# dashboard.net
KiCad netlist of a schematic drawn in EAGLE
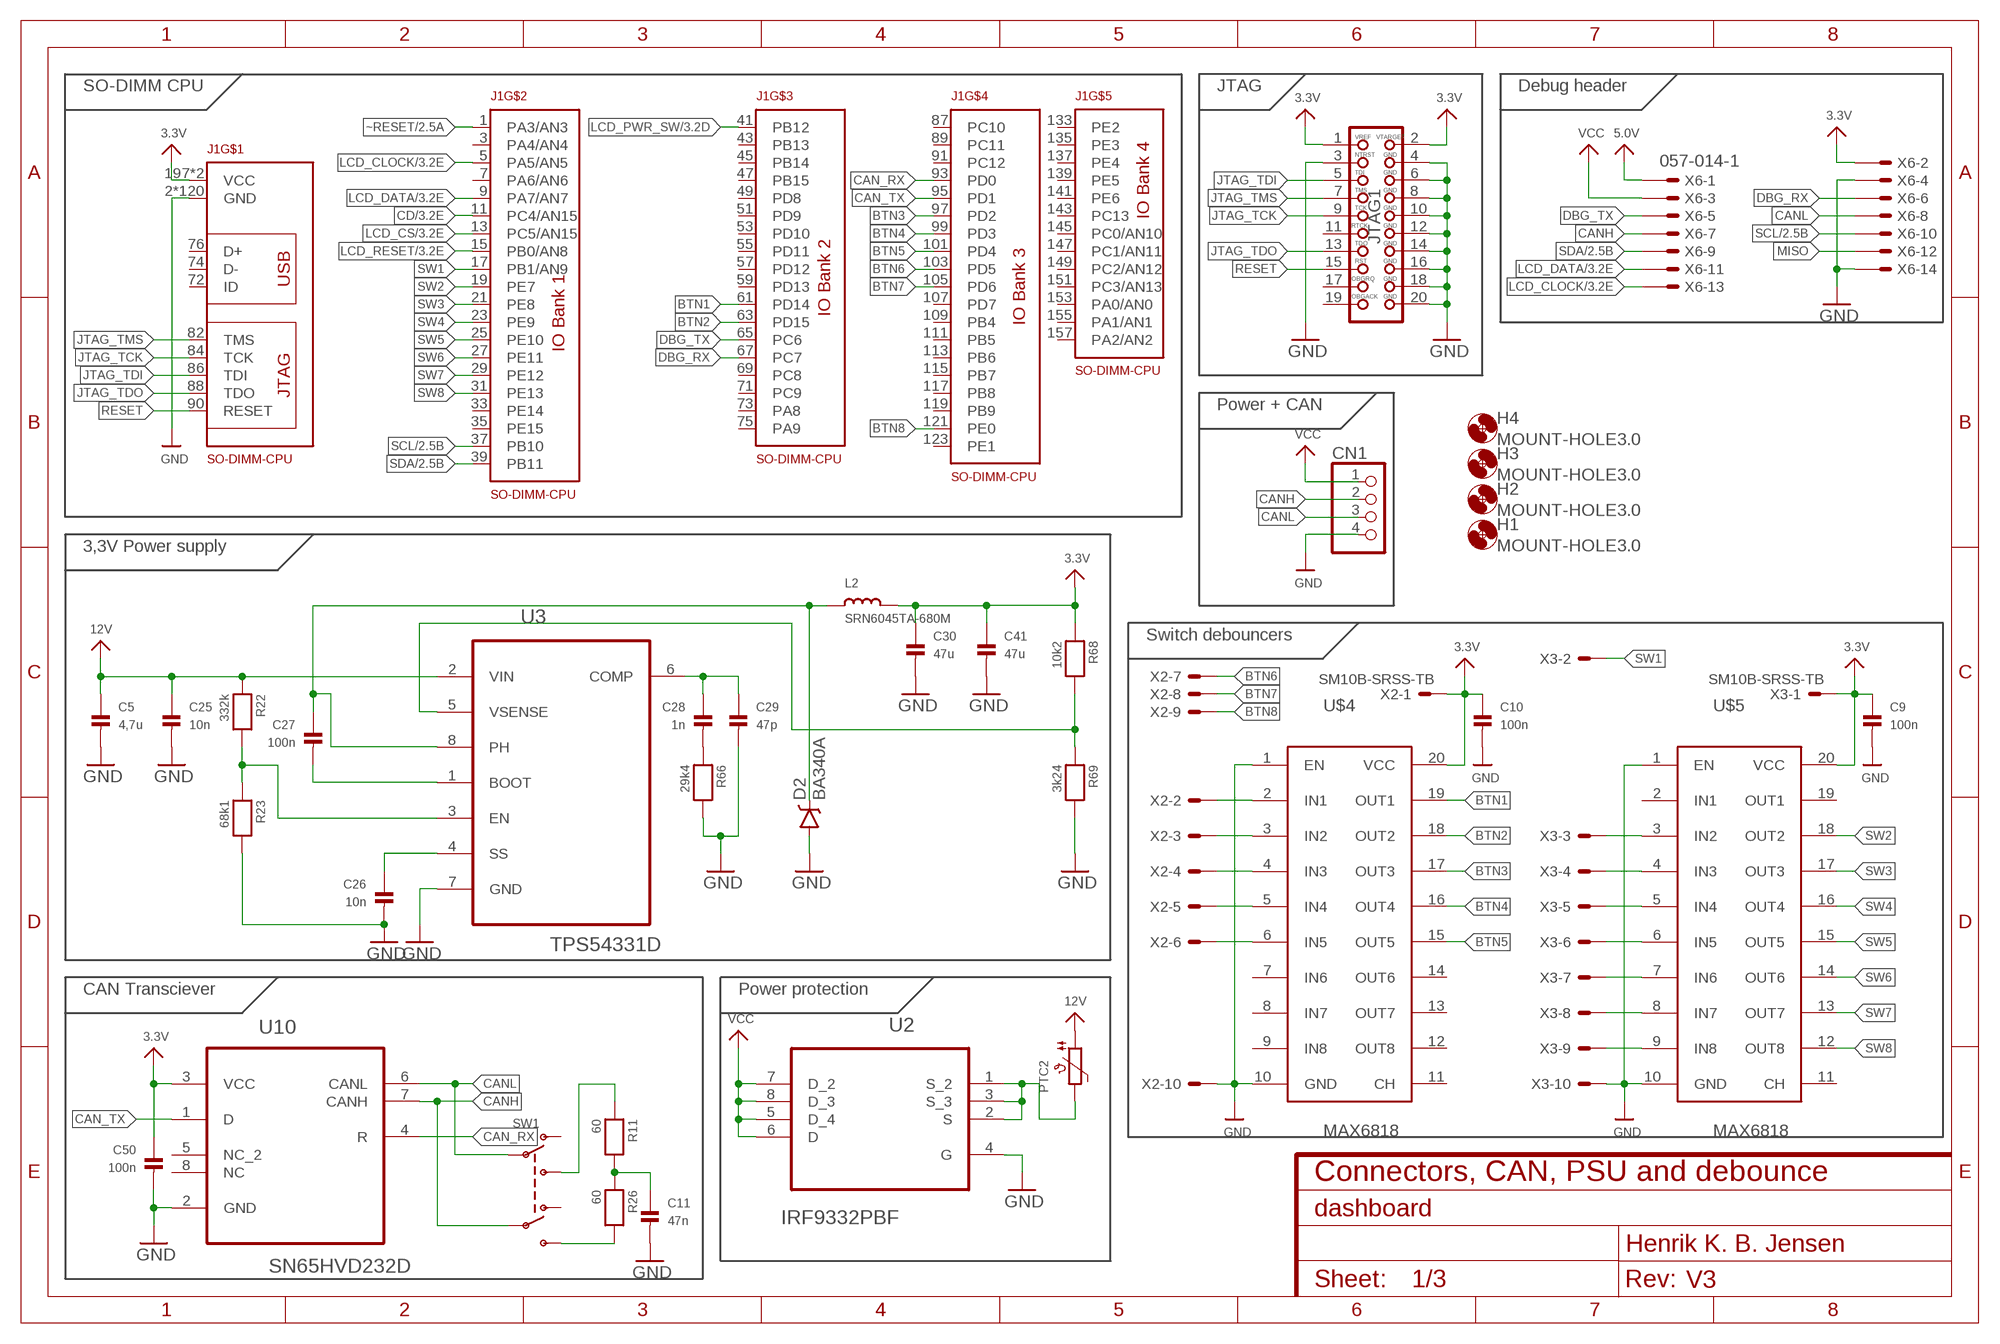
[diagram p0: schematic, sheet 1]
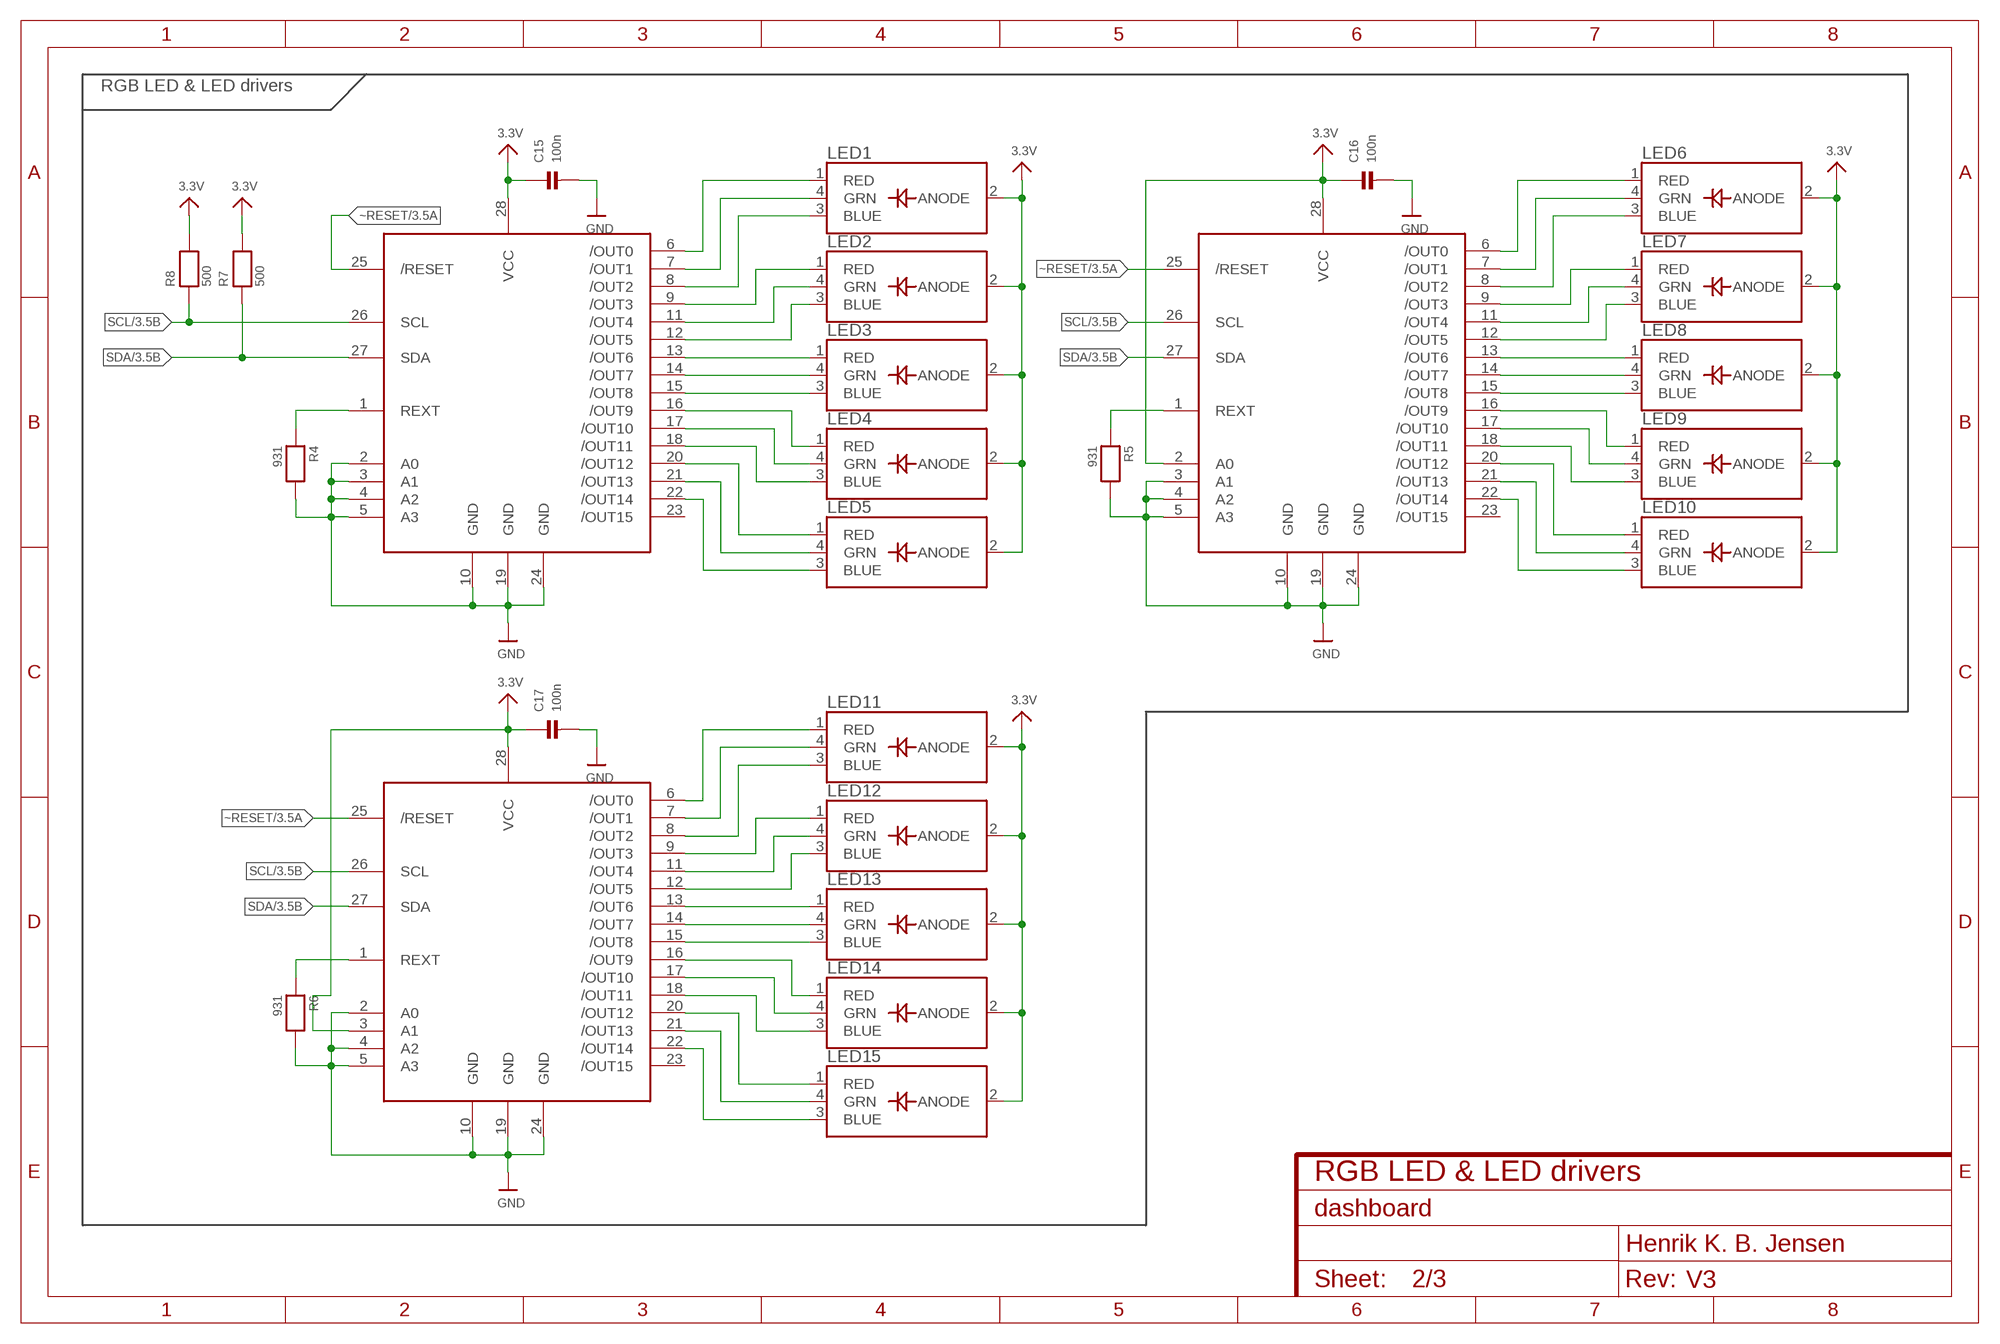
[diagram p1: schematic, sheet 2]
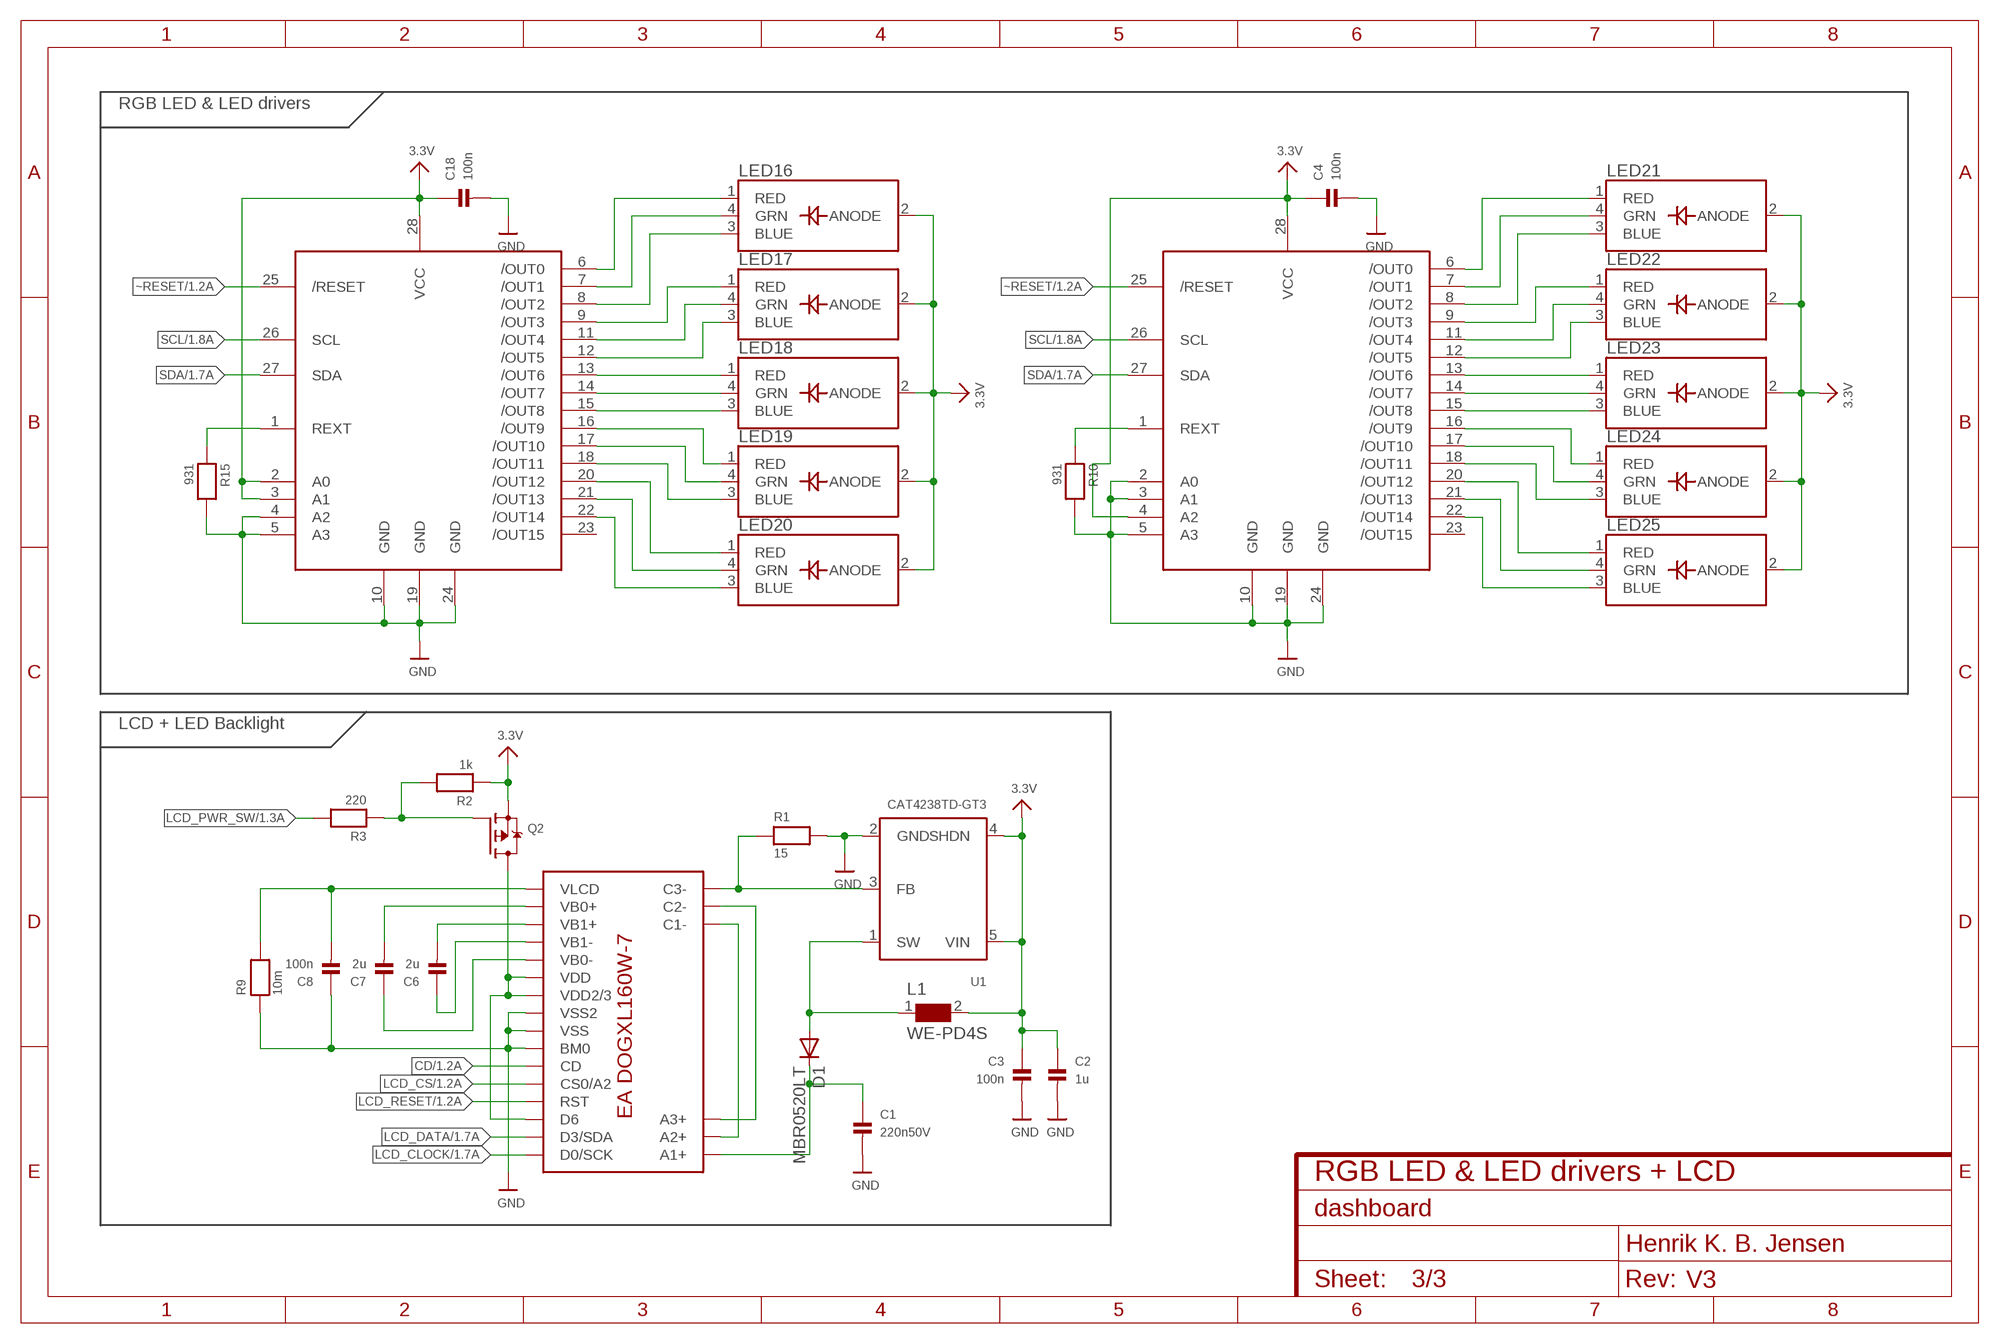
[diagram p2: schematic, sheet 3]

(export (version "E")
  (design (tool "Eeschema 10.0.6"))
  (components
    (comp (ref "C5")
      (value "4,7u")
      (footprint "eagle-import:_0805")
      (libsource (lib "eagle-import") (part "CAP_CERAMIC_0805"))
    )
    (comp (ref "C9")
      (value "100n")
      (footprint "eagle-import:_0603")
      (libsource (lib "eagle-import") (part "CAP_CERAMIC_0603"))
    )
    (comp (ref "C10")
      (value "100n")
      (footprint "eagle-import:_0603")
      (libsource (lib "eagle-import") (part "CAP_CERAMIC_0603"))
    )
    (comp (ref "C11")
      (value "47n")
      (footprint "eagle-import:_0603")
      (libsource (lib "eagle-import") (part "CAP_CERAMIC_0603"))
    )
    (comp (ref "C25")
      (value "10n")
      (footprint "eagle-import:_0603")
      (libsource (lib "eagle-import") (part "CAP_CERAMIC_0603"))
    )
    (comp (ref "C26")
      (value "10n")
      (footprint "eagle-import:_0603")
      (libsource (lib "eagle-import") (part "CAP_CERAMIC_0603"))
    )
    (comp (ref "C27")
      (value "100n")
      (footprint "eagle-import:_0603")
      (libsource (lib "eagle-import") (part "CAP_CERAMIC_0603"))
    )
    (comp (ref "C28")
      (value "1n")
      (footprint "eagle-import:_0603")
      (libsource (lib "eagle-import") (part "CAP_CERAMIC_0603"))
    )
    (comp (ref "C29")
      (value "47p")
      (footprint "eagle-import:_0603")
      (libsource (lib "eagle-import") (part "CAP_CERAMIC_0603"))
    )
    (comp (ref "C30")
      (value "47u")
      (footprint "eagle-import:_0805")
      (libsource (lib "eagle-import") (part "CAP_CERAMIC_0805"))
    )
    (comp (ref "C41")
      (value "47u")
      (footprint "eagle-import:_0805")
      (libsource (lib "eagle-import") (part "CAP_CERAMIC_0805"))
    )
    (comp (ref "C50")
      (value "100n")
      (footprint "eagle-import:_0603")
      (libsource (lib "eagle-import") (part "CAP_CERAMIC_0603"))
    )
    (comp (ref "CN1")
      (value "JST_4PIN")
      (footprint "eagle-import:JSTPH4")
      (libsource (lib "eagle-import") (part "JST_4PIN"))
    )
    (comp (ref "D2")
      (value "BA340A")
      (footprint "eagle-import:SMA-DIODE")
      (libsource (lib "eagle-import") (part "B340A"))
    )
    (comp (ref "H1")
      (value "MOUNT-HOLE3.0")
      (footprint "eagle-import:3,0")
      (libsource (lib "eagle-import") (part "MOUNT-HOLE3.0"))
    )
    (comp (ref "H2")
      (value "MOUNT-HOLE3.0")
      (footprint "eagle-import:3,0")
      (libsource (lib "eagle-import") (part "MOUNT-HOLE3.0"))
    )
    (comp (ref "H3")
      (value "MOUNT-HOLE3.0")
      (footprint "eagle-import:3,0")
      (libsource (lib "eagle-import") (part "MOUNT-HOLE3.0"))
    )
    (comp (ref "H4")
      (value "MOUNT-HOLE3.0")
      (footprint "eagle-import:3,0")
      (libsource (lib "eagle-import") (part "MOUNT-HOLE3.0"))
    )
    (comp (ref "J1")
      (value "SO-DIMM-CPU")
      (footprint "eagle-import:SODIMM-CONNECTOR-2.5V")
      (libsource (lib "eagle-import") (part "SO-DIMM-CPU"))
    )
    (comp (ref "JTAG1")
      (value "JTAG-ARM")
      (footprint "eagle-import:JTAG-ARM")
      (libsource (lib "eagle-import") (part "JTAG-ARM"))
    )
    (comp (ref "L2")
      (value "SRN6045TA-680M")
      (footprint "eagle-import:INDUCTOR_6X6MM_TDK_VLC6045")
      (libsource (lib "eagle-import") (part "INDUCTORTDK_VLC6045"))
    )
    (comp (ref "PTC2")
      (value "PTC1812")
      (footprint "eagle-import:PTC1812")
      (libsource (lib "eagle-import") (part "PTC1812"))
    )
    (comp (ref "R11")
      (value "60")
      (footprint "eagle-import:_0603")
      (libsource (lib "eagle-import") (part "RESISTOR_0603"))
    )
    (comp (ref "R22")
      (value "332k")
      (footprint "eagle-import:_0603")
      (libsource (lib "eagle-import") (part "RESISTOR_0603"))
    )
    (comp (ref "R23")
      (value "68k1")
      (footprint "eagle-import:_0603")
      (libsource (lib "eagle-import") (part "RESISTOR_0603"))
    )
    (comp (ref "R26")
      (value "60")
      (footprint "eagle-import:_0603")
      (libsource (lib "eagle-import") (part "RESISTOR_0603"))
    )
    (comp (ref "R66")
      (value "29k4")
      (footprint "eagle-import:_0603")
      (libsource (lib "eagle-import") (part "RESISTOR_0603"))
    )
    (comp (ref "R68")
      (value "10k2")
      (footprint "eagle-import:_0603")
      (libsource (lib "eagle-import") (part "RESISTOR_0603"))
    )
    (comp (ref "R69")
      (value "3k24")
      (footprint "eagle-import:_0603")
      (libsource (lib "eagle-import") (part "RESISTOR_0603"))
    )
    (comp (ref "SW1")
      (value "SWITCH_DPDT")
      (footprint "eagle-import:DPDT_SMT_JS202011SCQN")
      (libsource (lib "eagle-import") (part "SWITCH_DPDT"))
    )
    (comp (ref "U$4")
      (value "MAX6818")
      (footprint "eagle-import:SOP20")
      (libsource (lib "eagle-import") (part "MAX6818"))
    )
    (comp (ref "U$5")
      (value "MAX6818")
      (footprint "eagle-import:SOP20")
      (libsource (lib "eagle-import") (part "MAX6818"))
    )
    (comp (ref "U2")
      (value "IRF9332PBF")
      (footprint "eagle-import:SOIC127P600X175-8N")
      (libsource (lib "eagle-import") (part "IRF9332PBF"))
    )
    (comp (ref "U3")
      (value "TPS54331D")
      (footprint "eagle-import:SOIC127P600X175-8N")
      (libsource (lib "eagle-import") (part "TPS54331D"))
    )
    (comp (ref "U10")
      (value "SN65HVD232D")
      (footprint "eagle-import:SOIC127P600X175-8N")
      (libsource (lib "eagle-import") (part "SN65HVD232D"))
    )
    (comp (ref "X2")
      (value "SM10B-SRSS-TB")
      (footprint "eagle-import:SM10B-SRSS-TB")
      (libsource (lib "eagle-import") (part "?M10B-SRSS-TBS"))
    )
    (comp (ref "X3")
      (value "SM10B-SRSS-TB")
      (footprint "eagle-import:SM10B-SRSS-TB")
      (libsource (lib "eagle-import") (part "?M10B-SRSS-TBS"))
    )
    (comp (ref "X6")
      (value "057-014-1")
      (footprint "eagle-import:057-014-1")
      (libsource (lib "eagle-import") (part "057-014-1"))
    )
    (comp (ref "C1")
      (value "220n50V")
      (footprint "eagle-import:_0805")
      (libsource (lib "eagle-import") (part "CAP_CERAMIC_0805"))
    )
    (comp (ref "C2")
      (value "1u")
      (footprint "eagle-import:_0805")
      (libsource (lib "eagle-import") (part "CAP_CERAMIC_0805"))
    )
    (comp (ref "C3")
      (value "100n")
      (footprint "eagle-import:_0603")
      (libsource (lib "eagle-import") (part "CAP_CERAMIC_0603"))
    )
    (comp (ref "C4")
      (value "100n")
      (footprint "eagle-import:_0603")
      (libsource (lib "eagle-import") (part "CAP_CERAMIC_0603"))
    )
    (comp (ref "C6")
      (value "2u")
      (footprint "eagle-import:_0805")
      (libsource (lib "eagle-import") (part "CAP_CERAMIC_0805"))
    )
    (comp (ref "C7")
      (value "2u")
      (footprint "eagle-import:_0805")
      (libsource (lib "eagle-import") (part "CAP_CERAMIC_0805"))
    )
    (comp (ref "C8")
      (value "100n")
      (footprint "eagle-import:_0603")
      (libsource (lib "eagle-import") (part "CAP_CERAMIC_0603"))
    )
    (comp (ref "C18")
      (value "100n")
      (footprint "eagle-import:_0603")
      (libsource (lib "eagle-import") (part "CAP_CERAMIC_0603"))
    )
    (comp (ref "D1")
      (value "MBR0520LT")
      (footprint "eagle-import:SOD123")
      (libsource (lib "eagle-import") (part "MBR0520LT"))
    )
    (comp (ref "L1")
      (value "WE-PD4S")
      (footprint "eagle-import:S")
      (fields (field (name "MPN") "7445501"))
      (libsource (lib "eagle-import") (part "WE-PD4_S-7445501"))
    )
    (comp (ref "LED16")
      (value "LED_RGB_PLCC4")
      (footprint "eagle-import:RGBLED_PLCC4")
      (libsource (lib "eagle-import") (part "LED_RGB_PLCC4"))
    )
    (comp (ref "LED17")
      (value "LED_RGB_PLCC4")
      (footprint "eagle-import:RGBLED_PLCC4")
      (libsource (lib "eagle-import") (part "LED_RGB_PLCC4"))
    )
    (comp (ref "LED18")
      (value "LED_RGB_PLCC4")
      (footprint "eagle-import:RGBLED_PLCC4")
      (libsource (lib "eagle-import") (part "LED_RGB_PLCC4"))
    )
    (comp (ref "LED19")
      (value "LED_RGB_PLCC4")
      (footprint "eagle-import:RGBLED_PLCC4")
      (libsource (lib "eagle-import") (part "LED_RGB_PLCC4"))
    )
    (comp (ref "LED20")
      (value "LED_RGB_PLCC4")
      (footprint "eagle-import:RGBLED_PLCC4")
      (libsource (lib "eagle-import") (part "LED_RGB_PLCC4"))
    )
    (comp (ref "LED21")
      (value "LED_RGB_PLCC4")
      (footprint "eagle-import:RGBLED_PLCC4")
      (libsource (lib "eagle-import") (part "LED_RGB_PLCC4"))
    )
    (comp (ref "LED22")
      (value "LED_RGB_PLCC4")
      (footprint "eagle-import:RGBLED_PLCC4")
      (libsource (lib "eagle-import") (part "LED_RGB_PLCC4"))
    )
    (comp (ref "LED23")
      (value "LED_RGB_PLCC4")
      (footprint "eagle-import:RGBLED_PLCC4")
      (libsource (lib "eagle-import") (part "LED_RGB_PLCC4"))
    )
    (comp (ref "LED24")
      (value "LED_RGB_PLCC4")
      (footprint "eagle-import:RGBLED_PLCC4")
      (libsource (lib "eagle-import") (part "LED_RGB_PLCC4"))
    )
    (comp (ref "LED25")
      (value "LED_RGB_PLCC4")
      (footprint "eagle-import:RGBLED_PLCC4")
      (libsource (lib "eagle-import") (part "LED_RGB_PLCC4"))
    )
    (comp (ref "Q2")
      (value "MOSFET-PWIDE")
      (footprint "eagle-import:SOT23-WIDE")
      (libsource (lib "eagle-import") (part "MOSFET-PWIDE"))
    )
    (comp (ref "R1")
      (value "15")
      (footprint "eagle-import:_0603")
      (libsource (lib "eagle-import") (part "RESISTOR_0603"))
    )
    (comp (ref "R2")
      (value "1k")
      (footprint "eagle-import:_0603")
      (libsource (lib "eagle-import") (part "RESISTOR_0603"))
    )
    (comp (ref "R3")
      (value "220")
      (footprint "eagle-import:_0603")
      (libsource (lib "eagle-import") (part "RESISTOR_0603"))
    )
    (comp (ref "R9")
      (value "10m")
      (footprint "eagle-import:_0805")
      (libsource (lib "eagle-import") (part "RESISTOR_0805"))
    )
    (comp (ref "R10")
      (value "931")
      (footprint "eagle-import:_0603")
      (libsource (lib "eagle-import") (part "RESISTOR_0603"))
    )
    (comp (ref "R15")
      (value "931")
      (footprint "eagle-import:_0603")
      (libsource (lib "eagle-import") (part "RESISTOR_0603"))
    )
    (comp (ref "U$8")
      (value "TLC59116")
      (footprint "eagle-import:TSSOP28")
      (libsource (lib "eagle-import") (part "TLC59116"))
    )
    (comp (ref "U$10")
      (value "EA-DOGXL160W-7")
      (footprint "eagle-import:EA-DOGXL160W-7")
      (libsource (lib "eagle-import") (part "EA-DOGXL160W-7"))
    )
    (comp (ref "U$51")
      (value "TLC59116")
      (footprint "eagle-import:TSSOP28")
      (libsource (lib "eagle-import") (part "TLC59116"))
    )
    (comp (ref "U1")
      (value "CAT4238TD-GT3")
      (footprint "eagle-import:SOT23-5")
      (libsource (lib "eagle-import") (part "FAN5331"))
    )
    (comp (ref "C15")
      (value "100n")
      (footprint "eagle-import:_0603")
      (libsource (lib "eagle-import") (part "CAP_CERAMIC_0603"))
    )
    (comp (ref "C16")
      (value "100n")
      (footprint "eagle-import:_0603")
      (libsource (lib "eagle-import") (part "CAP_CERAMIC_0603"))
    )
    (comp (ref "C17")
      (value "100n")
      (footprint "eagle-import:_0603")
      (libsource (lib "eagle-import") (part "CAP_CERAMIC_0603"))
    )
    (comp (ref "LED1")
      (value "LED_RGB_PLCC4")
      (footprint "eagle-import:RGBLED_PLCC4")
      (libsource (lib "eagle-import") (part "LED_RGB_PLCC4"))
    )
    (comp (ref "LED2")
      (value "LED_RGB_PLCC4")
      (footprint "eagle-import:RGBLED_PLCC4")
      (libsource (lib "eagle-import") (part "LED_RGB_PLCC4"))
    )
    (comp (ref "LED3")
      (value "LED_RGB_PLCC4")
      (footprint "eagle-import:RGBLED_PLCC4")
      (libsource (lib "eagle-import") (part "LED_RGB_PLCC4"))
    )
    (comp (ref "LED4")
      (value "LED_RGB_PLCC4")
      (footprint "eagle-import:RGBLED_PLCC4")
      (libsource (lib "eagle-import") (part "LED_RGB_PLCC4"))
    )
    (comp (ref "LED5")
      (value "LED_RGB_PLCC4")
      (footprint "eagle-import:RGBLED_PLCC4")
      (libsource (lib "eagle-import") (part "LED_RGB_PLCC4"))
    )
    (comp (ref "LED6")
      (value "LED_RGB_PLCC4")
      (footprint "eagle-import:RGBLED_PLCC4")
      (libsource (lib "eagle-import") (part "LED_RGB_PLCC4"))
    )
    (comp (ref "LED7")
      (value "LED_RGB_PLCC4")
      (footprint "eagle-import:RGBLED_PLCC4")
      (libsource (lib "eagle-import") (part "LED_RGB_PLCC4"))
    )
    (comp (ref "LED8")
      (value "LED_RGB_PLCC4")
      (footprint "eagle-import:RGBLED_PLCC4")
      (libsource (lib "eagle-import") (part "LED_RGB_PLCC4"))
    )
    (comp (ref "LED9")
      (value "LED_RGB_PLCC4")
      (footprint "eagle-import:RGBLED_PLCC4")
      (libsource (lib "eagle-import") (part "LED_RGB_PLCC4"))
    )
    (comp (ref "LED10")
      (value "LED_RGB_PLCC4")
      (footprint "eagle-import:RGBLED_PLCC4")
      (libsource (lib "eagle-import") (part "LED_RGB_PLCC4"))
    )
    (comp (ref "LED11")
      (value "LED_RGB_PLCC4")
      (footprint "eagle-import:RGBLED_PLCC4")
      (libsource (lib "eagle-import") (part "LED_RGB_PLCC4"))
    )
    (comp (ref "LED12")
      (value "LED_RGB_PLCC4")
      (footprint "eagle-import:RGBLED_PLCC4")
      (libsource (lib "eagle-import") (part "LED_RGB_PLCC4"))
    )
    (comp (ref "LED13")
      (value "LED_RGB_PLCC4")
      (footprint "eagle-import:RGBLED_PLCC4")
      (libsource (lib "eagle-import") (part "LED_RGB_PLCC4"))
    )
    (comp (ref "LED14")
      (value "LED_RGB_PLCC4")
      (footprint "eagle-import:RGBLED_PLCC4")
      (libsource (lib "eagle-import") (part "LED_RGB_PLCC4"))
    )
    (comp (ref "LED15")
      (value "LED_RGB_PLCC4")
      (footprint "eagle-import:RGBLED_PLCC4")
      (libsource (lib "eagle-import") (part "LED_RGB_PLCC4"))
    )
    (comp (ref "R4")
      (value "931")
      (footprint "eagle-import:_0603")
      (libsource (lib "eagle-import") (part "RESISTOR_0603"))
    )
    (comp (ref "R5")
      (value "931")
      (footprint "eagle-import:_0603")
      (libsource (lib "eagle-import") (part "RESISTOR_0603"))
    )
    (comp (ref "R6")
      (value "931")
      (footprint "eagle-import:_0603")
      (libsource (lib "eagle-import") (part "RESISTOR_0603"))
    )
    (comp (ref "R7")
      (value "500")
      (footprint "eagle-import:_0603")
      (libsource (lib "eagle-import") (part "RESISTOR_0603"))
    )
    (comp (ref "R8")
      (value "500")
      (footprint "eagle-import:_0603")
      (libsource (lib "eagle-import") (part "RESISTOR_0603"))
    )
    (comp (ref "U$30")
      (value "TLC59116")
      (footprint "eagle-import:TSSOP28")
      (libsource (lib "eagle-import") (part "TLC59116"))
    )
    (comp (ref "U$33")
      (value "TLC59116")
      (footprint "eagle-import:TSSOP28")
      (libsource (lib "eagle-import") (part "TLC59116"))
    )
    (comp (ref "U$36")
      (value "TLC59116")
      (footprint "eagle-import:TSSOP28")
      (libsource (lib "eagle-import") (part "TLC59116"))
    )
  )
  (nets
    (net (code "1") (name "3.3V") (class "Default")
      (node (ref "C10") (pin "1") (pinfunction "P$1_1") (pintype "passive"))
      (node (ref "C15") (pin "1") (pinfunction "P$1_1") (pintype "passive"))
      (node (ref "C16") (pin "1") (pinfunction "P$1_1") (pintype "passive"))
      (node (ref "C17") (pin "1") (pinfunction "P$1_1") (pintype "passive"))
      (node (ref "C18") (pin "1") (pinfunction "P$1_1") (pintype "passive"))
      (node (ref "C2") (pin "1") (pinfunction "P$1_1") (pintype "passive"))
      (node (ref "C3") (pin "1") (pinfunction "P$1_1") (pintype "passive"))
      (node (ref "C30") (pin "1") (pinfunction "P$1_1") (pintype "passive"))
      (node (ref "C4") (pin "1") (pinfunction "P$1_1") (pintype "passive"))
      (node (ref "C41") (pin "1") (pinfunction "P$1_1") (pintype "passive"))
      (node (ref "C50") (pin "1") (pinfunction "P$1_1") (pintype "passive"))
      (node (ref "C9") (pin "1") (pinfunction "P$1_1") (pintype "passive"))
      (node (ref "J1") (pin "197") (pinfunction "VCC_197") (pintype "bidirectional"))
      (node (ref "J1") (pin "199") (pinfunction "VCC_199") (pintype "bidirectional"))
      (node (ref "JTAG1") (pin "1") (pinfunction "1_1") (pintype "passive"))
      (node (ref "JTAG1") (pin "2") (pinfunction "2_2") (pintype "passive"))
      (node (ref "L1") (pin "2") (pinfunction "2_2") (pintype "passive"))
      (node (ref "L2") (pin "P$2") (pinfunction "2_P$2") (pintype "passive"))
      (node (ref "LED1") (pin "2") (pinfunction "ANODE_2") (pintype "power_in"))
      (node (ref "LED10") (pin "2") (pinfunction "ANODE_2") (pintype "power_in"))
      (node (ref "LED11") (pin "2") (pinfunction "ANODE_2") (pintype "power_in"))
      (node (ref "LED12") (pin "2") (pinfunction "ANODE_2") (pintype "power_in"))
      (node (ref "LED13") (pin "2") (pinfunction "ANODE_2") (pintype "power_in"))
      (node (ref "LED14") (pin "2") (pinfunction "ANODE_2") (pintype "power_in"))
      (node (ref "LED15") (pin "2") (pinfunction "ANODE_2") (pintype "power_in"))
      (node (ref "LED16") (pin "2") (pinfunction "ANODE_2") (pintype "power_in"))
      (node (ref "LED17") (pin "2") (pinfunction "ANODE_2") (pintype "power_in"))
      (node (ref "LED18") (pin "2") (pinfunction "ANODE_2") (pintype "power_in"))
      (node (ref "LED19") (pin "2") (pinfunction "ANODE_2") (pintype "power_in"))
      (node (ref "LED2") (pin "2") (pinfunction "ANODE_2") (pintype "power_in"))
      (node (ref "LED20") (pin "2") (pinfunction "ANODE_2") (pintype "power_in"))
      (node (ref "LED21") (pin "2") (pinfunction "ANODE_2") (pintype "power_in"))
      (node (ref "LED22") (pin "2") (pinfunction "ANODE_2") (pintype "power_in"))
      (node (ref "LED23") (pin "2") (pinfunction "ANODE_2") (pintype "power_in"))
      (node (ref "LED24") (pin "2") (pinfunction "ANODE_2") (pintype "power_in"))
      (node (ref "LED25") (pin "2") (pinfunction "ANODE_2") (pintype "power_in"))
      (node (ref "LED3") (pin "2") (pinfunction "ANODE_2") (pintype "power_in"))
      (node (ref "LED4") (pin "2") (pinfunction "ANODE_2") (pintype "power_in"))
      (node (ref "LED5") (pin "2") (pinfunction "ANODE_2") (pintype "power_in"))
      (node (ref "LED6") (pin "2") (pinfunction "ANODE_2") (pintype "power_in"))
      (node (ref "LED7") (pin "2") (pinfunction "ANODE_2") (pintype "power_in"))
      (node (ref "LED8") (pin "2") (pinfunction "ANODE_2") (pintype "power_in"))
      (node (ref "LED9") (pin "2") (pinfunction "ANODE_2") (pintype "power_in"))
      (node (ref "Q2") (pin "2") (pinfunction "S_2") (pintype "passive"))
      (node (ref "R2") (pin "1") (pinfunction "1_1") (pintype "passive"))
      (node (ref "R68") (pin "1") (pinfunction "1_1") (pintype "passive"))
      (node (ref "R7") (pin "2") (pinfunction "2_2") (pintype "passive"))
      (node (ref "R8") (pin "2") (pinfunction "2_2") (pintype "passive"))
      (node (ref "U$30") (pin "28") (pinfunction "VCC_28") (pintype "bidirectional"))
      (node (ref "U$33") (pin "2") (pinfunction "A0_2") (pintype "bidirectional"))
      (node (ref "U$33") (pin "28") (pinfunction "VCC_28") (pintype "bidirectional"))
      (node (ref "U$36") (pin "28") (pinfunction "VCC_28") (pintype "bidirectional"))
      (node (ref "U$36") (pin "3") (pinfunction "A1_3") (pintype "bidirectional"))
      (node (ref "U$4") (pin "20") (pinfunction "VCC_20") (pintype "power_in"))
      (node (ref "U$5") (pin "20") (pinfunction "VCC_20") (pintype "power_in"))
      (node (ref "U$51") (pin "2") (pinfunction "A0_2") (pintype "bidirectional"))
      (node (ref "U$51") (pin "28") (pinfunction "VCC_28") (pintype "bidirectional"))
      (node (ref "U$51") (pin "3") (pinfunction "A1_3") (pintype "bidirectional"))
      (node (ref "U$8") (pin "28") (pinfunction "VCC_28") (pintype "bidirectional"))
      (node (ref "U$8") (pin "4") (pinfunction "A2_4") (pintype "bidirectional"))
      (node (ref "U1") (pin "4") (pinfunction "SHDN_4") (pintype "bidirectional"))
      (node (ref "U1") (pin "5") (pinfunction "VIN_5") (pintype "bidirectional"))
      (node (ref "U10") (pin "3") (pinfunction "VCC_3") (pintype "power_in"))
      (node (ref "X2") (pin "1") (pinfunction "S_1") (pintype "passive"))
      (node (ref "X3") (pin "1") (pinfunction "S_1") (pintype "passive"))
      (node (ref "X6") (pin "2") (pinfunction "S_2") (pintype "passive"))
    )
    (net (code "2") (name "5.0V") (class "Default")
      (node (ref "X6") (pin "1") (pinfunction "S_1") (pintype "passive"))
    )
    (net (code "3") (name "12V") (class "Default")
      (node (ref "C25") (pin "1") (pinfunction "P$1_1") (pintype "passive"))
      (node (ref "C5") (pin "1") (pinfunction "P$1_1") (pintype "passive"))
      (node (ref "PTC2") (pin "P$1") (pinfunction "1_P$1") (pintype "passive"))
      (node (ref "R22") (pin "1") (pinfunction "1_1") (pintype "passive"))
      (node (ref "U3") (pin "2") (pinfunction "VIN_2") (pintype "input"))
    )
    (net (code "4") (name "BTN1") (class "Default")
      (node (ref "J1") (pin "61") (pinfunction "PD14_61") (pintype "bidirectional"))
      (node (ref "U$4") (pin "19") (pinfunction "OUT1_19") (pintype "bidirectional"))
    )
    (net (code "5") (name "BTN2") (class "Default")
      (node (ref "J1") (pin "63") (pinfunction "PD15_63") (pintype "bidirectional"))
      (node (ref "U$4") (pin "18") (pinfunction "OUT2_18") (pintype "bidirectional"))
    )
    (net (code "6") (name "BTN3") (class "Default")
      (node (ref "J1") (pin "97") (pinfunction "PD2_97") (pintype "bidirectional"))
      (node (ref "U$4") (pin "17") (pinfunction "OUT3_17") (pintype "bidirectional"))
    )
    (net (code "7") (name "BTN4") (class "Default")
      (node (ref "J1") (pin "99") (pinfunction "PD3_99") (pintype "bidirectional"))
      (node (ref "U$4") (pin "16") (pinfunction "OUT4_16") (pintype "bidirectional"))
    )
    (net (code "8") (name "BTN5") (class "Default")
      (node (ref "J1") (pin "101") (pinfunction "PD4_101") (pintype "bidirectional"))
      (node (ref "U$4") (pin "15") (pinfunction "OUT5_15") (pintype "bidirectional"))
    )
    (net (code "9") (name "BTN6") (class "Default")
      (node (ref "J1") (pin "103") (pinfunction "PD5_103") (pintype "bidirectional"))
      (node (ref "X2") (pin "7") (pinfunction "S_7") (pintype "passive"))
    )
    (net (code "10") (name "BTN7") (class "Default")
      (node (ref "J1") (pin "105") (pinfunction "PD6_105") (pintype "bidirectional"))
      (node (ref "X2") (pin "8") (pinfunction "S_8") (pintype "passive"))
    )
    (net (code "11") (name "BTN8") (class "Default")
      (node (ref "J1") (pin "121") (pinfunction "PE0_121") (pintype "bidirectional"))
      (node (ref "X2") (pin "9") (pinfunction "S_9") (pintype "passive"))
    )
    (net (code "12") (name "CANH") (class "Default")
      (node (ref "CN1") (pin "2") (pinfunction "2_2") (pintype "passive"))
      (node (ref "SW1") (pin "P$5") (pinfunction "P2_P$5") (pintype "passive"))
      (node (ref "U10") (pin "7") (pinfunction "CANH_7") (pintype "output"))
      (node (ref "X6") (pin "7") (pinfunction "S_7") (pintype "passive"))
    )
    (net (code "13") (name "CANL") (class "Default")
      (node (ref "CN1") (pin "3") (pinfunction "3_3") (pintype "passive"))
      (node (ref "SW1") (pin "P$2") (pinfunction "P1_P$2") (pintype "passive"))
      (node (ref "U10") (pin "6") (pinfunction "CANL_6") (pintype "output"))
      (node (ref "X6") (pin "8") (pinfunction "S_8") (pintype "passive"))
    )
    (net (code "14") (name "CAN_RX") (class "Default")
      (node (ref "J1") (pin "93") (pinfunction "PD0_93") (pintype "bidirectional"))
      (node (ref "U10") (pin "4") (pinfunction "R_4") (pintype "output"))
    )
    (net (code "15") (name "CAN_TX") (class "Default")
      (node (ref "J1") (pin "95") (pinfunction "PD1_95") (pintype "bidirectional"))
      (node (ref "U10") (pin "1") (pinfunction "D_1") (pintype "input"))
    )
    (net (code "16") (name "CD") (class "Default")
      (node (ref "J1") (pin "11") (pinfunction "PC4/AN15_11") (pintype "bidirectional"))
      (node (ref "U$10") (pin "P$27") (pinfunction "CD_P$27") (pintype "bidirectional"))
    )
    (net (code "17") (name "DBG_RX") (class "Default")
      (node (ref "J1") (pin "67") (pinfunction "PC7_67") (pintype "bidirectional"))
      (node (ref "X6") (pin "6") (pinfunction "S_6") (pintype "passive"))
    )
    (net (code "18") (name "DBG_TX") (class "Default")
      (node (ref "J1") (pin "65") (pinfunction "PC6_65") (pintype "bidirectional"))
      (node (ref "X6") (pin "5") (pinfunction "S_5") (pintype "passive"))
    )
    (net (code "19") (name "GND") (class "Default")
      (node (ref "C1") (pin "2") (pinfunction "P$2_2") (pintype "passive"))
      (node (ref "C10") (pin "2") (pinfunction "P$2_2") (pintype "passive"))
      (node (ref "C11") (pin "2") (pinfunction "P$2_2") (pintype "passive"))
      (node (ref "C15") (pin "2") (pinfunction "P$2_2") (pintype "passive"))
      (node (ref "C16") (pin "2") (pinfunction "P$2_2") (pintype "passive"))
      (node (ref "C17") (pin "2") (pinfunction "P$2_2") (pintype "passive"))
      (node (ref "C18") (pin "2") (pinfunction "P$2_2") (pintype "passive"))
      (node (ref "C2") (pin "2") (pinfunction "P$2_2") (pintype "passive"))
      (node (ref "C25") (pin "2") (pinfunction "P$2_2") (pintype "passive"))
      (node (ref "C26") (pin "2") (pinfunction "P$2_2") (pintype "passive"))
      (node (ref "C29") (pin "2") (pinfunction "P$2_2") (pintype "passive"))
      (node (ref "C3") (pin "2") (pinfunction "P$2_2") (pintype "passive"))
      (node (ref "C30") (pin "2") (pinfunction "P$2_2") (pintype "passive"))
      (node (ref "C4") (pin "2") (pinfunction "P$2_2") (pintype "passive"))
      (node (ref "C41") (pin "2") (pinfunction "P$2_2") (pintype "passive"))
      (node (ref "C5") (pin "2") (pinfunction "P$2_2") (pintype "passive"))
      (node (ref "C50") (pin "2") (pinfunction "P$2_2") (pintype "passive"))
      (node (ref "C8") (pin "1") (pinfunction "P$1_1") (pintype "passive"))
      (node (ref "C9") (pin "2") (pinfunction "P$2_2") (pintype "passive"))
      (node (ref "CN1") (pin "4") (pinfunction "4_4") (pintype "passive"))
      (node (ref "D2") (pin "A") (pinfunction "A_A") (pintype "passive"))
      (node (ref "J1") (pin "10") (pinfunction "GND_10") (pintype "bidirectional"))
      (node (ref "J1") (pin "100") (pinfunction "GND_100") (pintype "bidirectional"))
      (node (ref "J1") (pin "102") (pinfunction "GND_102") (pintype "bidirectional"))
      (node (ref "J1") (pin "104") (pinfunction "GND_104") (pintype "bidirectional"))
      (node (ref "J1") (pin "106") (pinfunction "GND_106") (pintype "bidirectional"))
      (node (ref "J1") (pin "108") (pinfunction "GND_108") (pintype "bidirectional"))
      (node (ref "J1") (pin "110") (pinfunction "GND_110") (pintype "bidirectional"))
      (node (ref "J1") (pin "112") (pinfunction "GND_112") (pintype "bidirectional"))
      (node (ref "J1") (pin "114") (pinfunction "GND_114") (pintype "bidirectional"))
      (node (ref "J1") (pin "116") (pinfunction "GND_116") (pintype "bidirectional"))
      (node (ref "J1") (pin "118") (pinfunction "GND_118") (pintype "bidirectional"))
      (node (ref "J1") (pin "12") (pinfunction "GND_12") (pintype "bidirectional"))
      (node (ref "J1") (pin "120") (pinfunction "GND_120") (pintype "bidirectional"))
      (node (ref "J1") (pin "122") (pinfunction "GND_122") (pintype "bidirectional"))
      (node (ref "J1") (pin "124") (pinfunction "GND_124") (pintype "bidirectional"))
      (node (ref "J1") (pin "125") (pinfunction "GND_125") (pintype "bidirectional"))
      (node (ref "J1") (pin "126") (pinfunction "GND_126") (pintype "bidirectional"))
      (node (ref "J1") (pin "127") (pinfunction "GND_127") (pintype "bidirectional"))
      (node (ref "J1") (pin "128") (pinfunction "GND_128") (pintype "bidirectional"))
      (node (ref "J1") (pin "129") (pinfunction "GND_129") (pintype "bidirectional"))
      (node (ref "J1") (pin "130") (pinfunction "GND_130") (pintype "bidirectional"))
      (node (ref "J1") (pin "131") (pinfunction "GND_131") (pintype "bidirectional"))
      (node (ref "J1") (pin "132") (pinfunction "GND_132") (pintype "bidirectional"))
      (node (ref "J1") (pin "134") (pinfunction "GND_134") (pintype "bidirectional"))
      (node (ref "J1") (pin "136") (pinfunction "GND_136") (pintype "bidirectional"))
      (node (ref "J1") (pin "138") (pinfunction "GND_138") (pintype "bidirectional"))
      (node (ref "J1") (pin "14") (pinfunction "GND_14") (pintype "bidirectional"))
      (node (ref "J1") (pin "140") (pinfunction "GND_140") (pintype "bidirectional"))
      (node (ref "J1") (pin "142") (pinfunction "GND_142") (pintype "bidirectional"))
      (node (ref "J1") (pin "144") (pinfunction "GND_144") (pintype "bidirectional"))
      (node (ref "J1") (pin "146") (pinfunction "GND_146") (pintype "bidirectional"))
      (node (ref "J1") (pin "148") (pinfunction "GND_148") (pintype "bidirectional"))
      (node (ref "J1") (pin "150") (pinfunction "GND_150") (pintype "bidirectional"))
      (node (ref "J1") (pin "152") (pinfunction "GND_152") (pintype "bidirectional"))
      (node (ref "J1") (pin "154") (pinfunction "GND_154") (pintype "bidirectional"))
      (node (ref "J1") (pin "156") (pinfunction "GND_156") (pintype "bidirectional"))
      (node (ref "J1") (pin "158") (pinfunction "GND_158") (pintype "bidirectional"))
      (node (ref "J1") (pin "159") (pinfunction "GND_159") (pintype "bidirectional"))
      (node (ref "J1") (pin "16") (pinfunction "GND_16") (pintype "bidirectional"))
      (node (ref "J1") (pin "160") (pinfunction "GND_160") (pintype "bidirectional"))
      (node (ref "J1") (pin "161") (pinfunction "GND_161") (pintype "bidirectional"))
      (node (ref "J1") (pin "162") (pinfunction "GND_162") (pintype "bidirectional"))
      (node (ref "J1") (pin "163") (pinfunction "GND_163") (pintype "bidirectional"))
      (node (ref "J1") (pin "164") (pinfunction "GND_164") (pintype "bidirectional"))
      (node (ref "J1") (pin "165") (pinfunction "GND_165") (pintype "bidirectional"))
      (node (ref "J1") (pin "166") (pinfunction "GND_166") (pintype "bidirectional"))
      (node (ref "J1") (pin "167") (pinfunction "GND_167") (pintype "bidirectional"))
      (node (ref "J1") (pin "168") (pinfunction "GND_168") (pintype "bidirectional"))
      (node (ref "J1") (pin "169") (pinfunction "GND_169") (pintype "bidirectional"))
      (node (ref "J1") (pin "170") (pinfunction "GND_170") (pintype "bidirectional"))
      (node (ref "J1") (pin "171") (pinfunction "GND_171") (pintype "bidirectional"))
      (node (ref "J1") (pin "172") (pinfunction "GND_172") (pintype "bidirectional"))
      (node (ref "J1") (pin "173") (pinfunction "GND_173") (pintype "bidirectional"))
      (node (ref "J1") (pin "174") (pinfunction "GND_174") (pintype "bidirectional"))
      (node (ref "J1") (pin "175") (pinfunction "GND_175") (pintype "bidirectional"))
      (node (ref "J1") (pin "176") (pinfunction "GND_176") (pintype "bidirectional"))
      (node (ref "J1") (pin "177") (pinfunction "GND_177") (pintype "bidirectional"))
      (node (ref "J1") (pin "178") (pinfunction "GND_178") (pintype "bidirectional"))
      (node (ref "J1") (pin "179") (pinfunction "GND_179") (pintype "bidirectional"))
      (node (ref "J1") (pin "18") (pinfunction "GND_18") (pintype "bidirectional"))
      (node (ref "J1") (pin "180") (pinfunction "GND_180") (pintype "bidirectional"))
      (node (ref "J1") (pin "181") (pinfunction "GND_181") (pintype "bidirectional"))
      (node (ref "J1") (pin "182") (pinfunction "GND_182") (pintype "bidirectional"))
      (node (ref "J1") (pin "183") (pinfunction "GND_183") (pintype "bidirectional"))
      (node (ref "J1") (pin "184") (pinfunction "GND_184") (pintype "bidirectional"))
      (node (ref "J1") (pin "185") (pinfunction "GND_185") (pintype "bidirectional"))
      (node (ref "J1") (pin "186") (pinfunction "GND_186") (pintype "bidirectional"))
      (node (ref "J1") (pin "187") (pinfunction "GND_187") (pintype "bidirectional"))
      (node (ref "J1") (pin "188") (pinfunction "GND_188") (pintype "bidirectional"))
      (node (ref "J1") (pin "189") (pinfunction "GND_189") (pintype "bidirectional"))
      (node (ref "J1") (pin "190") (pinfunction "GND_190") (pintype "bidirectional"))
      (node (ref "J1") (pin "191") (pinfunction "GND_191") (pintype "bidirectional"))
      (node (ref "J1") (pin "192") (pinfunction "GND_192") (pintype "bidirectional"))
      (node (ref "J1") (pin "193") (pinfunction "GND_193") (pintype "bidirectional"))
      (node (ref "J1") (pin "194") (pinfunction "GND_194") (pintype "bidirectional"))
      (node (ref "J1") (pin "195") (pinfunction "GND_195") (pintype "bidirectional"))
      (node (ref "J1") (pin "196") (pinfunction "GND_196") (pintype "bidirectional"))
      (node (ref "J1") (pin "198") (pinfunction "GND_198") (pintype "bidirectional"))
      (node (ref "J1") (pin "2") (pinfunction "GND_2") (pintype "bidirectional"))
      (node (ref "J1") (pin "20") (pinfunction "GND_20") (pintype "bidirectional"))
      (node (ref "J1") (pin "200") (pinfunction "GND_200") (pintype "bidirectional"))
      (node (ref "J1") (pin "22") (pinfunction "GND_22") (pintype "bidirectional"))
      (node (ref "J1") (pin "24") (pinfunction "GND_24") (pintype "bidirectional"))
      (node (ref "J1") (pin "26") (pinfunction "GND_26") (pintype "bidirectional"))
      (node (ref "J1") (pin "28") (pinfunction "GND_28") (pintype "bidirectional"))
      (node (ref "J1") (pin "30") (pinfunction "GND_30") (pintype "bidirectional"))
      (node (ref "J1") (pin "32") (pinfunction "GND_32") (pintype "bidirectional"))
      (node (ref "J1") (pin "34") (pinfunction "GND_34") (pintype "bidirectional"))
      (node (ref "J1") (pin "36") (pinfunction "GND_36") (pintype "bidirectional"))
      (node (ref "J1") (pin "38") (pinfunction "GND_38") (pintype "bidirectional"))
      (node (ref "J1") (pin "4") (pinfunction "GND_4") (pintype "bidirectional"))
      (node (ref "J1") (pin "40") (pinfunction "GND_40") (pintype "bidirectional"))
      (node (ref "J1") (pin "42") (pinfunction "GND_42") (pintype "bidirectional"))
      (node (ref "J1") (pin "44") (pinfunction "GND_44") (pintype "bidirectional"))
      (node (ref "J1") (pin "46") (pinfunction "GND_46") (pintype "bidirectional"))
      (node (ref "J1") (pin "48") (pinfunction "GND_48") (pintype "bidirectional"))
      (node (ref "J1") (pin "50") (pinfunction "GND_50") (pintype "bidirectional"))
      (node (ref "J1") (pin "52") (pinfunction "GND_52") (pintype "bidirectional"))
      (node (ref "J1") (pin "54") (pinfunction "GND_54") (pintype "bidirectional"))
      (node (ref "J1") (pin "56") (pinfunction "GND_56") (pintype "bidirectional"))
      (node (ref "J1") (pin "58") (pinfunction "GND_58") (pintype "bidirectional"))
      (node (ref "J1") (pin "6") (pinfunction "GND_6") (pintype "bidirectional"))
      (node (ref "J1") (pin "60") (pinfunction "GND_60") (pintype "bidirectional"))
      (node (ref "J1") (pin "62") (pinfunction "GND_62") (pintype "bidirectional"))
      (node (ref "J1") (pin "64") (pinfunction "GND_64") (pintype "bidirectional"))
      (node (ref "J1") (pin "66") (pinfunction "GND_66") (pintype "bidirectional"))
      (node (ref "J1") (pin "68") (pinfunction "GND_68") (pintype "bidirectional"))
      (node (ref "J1") (pin "70") (pinfunction "GND_70") (pintype "bidirectional"))
      (node (ref "J1") (pin "77") (pinfunction "GND_77") (pintype "bidirectional"))
      (node (ref "J1") (pin "78") (pinfunction "GND_78") (pintype "bidirectional"))
      (node (ref "J1") (pin "79") (pinfunction "GND_79") (pintype "bidirectional"))
      (node (ref "J1") (pin "8") (pinfunction "GND_8") (pintype "bidirectional"))
      (node (ref "J1") (pin "80") (pinfunction "GND_80") (pintype "bidirectional"))
      (node (ref "J1") (pin "81") (pinfunction "GND_81") (pintype "bidirectional"))
      (node (ref "J1") (pin "83") (pinfunction "GND_83") (pintype "bidirectional"))
      (node (ref "J1") (pin "85") (pinfunction "GND_85") (pintype "bidirectional"))
      (node (ref "J1") (pin "92") (pinfunction "GND_92") (pintype "bidirectional"))
      (node (ref "J1") (pin "94") (pinfunction "GND_94") (pintype "bidirectional"))
      (node (ref "J1") (pin "96") (pinfunction "GND_96") (pintype "bidirectional"))
      (node (ref "J1") (pin "98") (pinfunction "GND_98") (pintype "bidirectional"))
      (node (ref "JTAG1") (pin "10") (pinfunction "10_10") (pintype "passive"))
      (node (ref "JTAG1") (pin "12") (pinfunction "12_12") (pintype "passive"))
      (node (ref "JTAG1") (pin "14") (pinfunction "14_14") (pintype "passive"))
      (node (ref "JTAG1") (pin "16") (pinfunction "16_16") (pintype "passive"))
      (node (ref "JTAG1") (pin "18") (pinfunction "18_18") (pintype "passive"))
      (node (ref "JTAG1") (pin "20") (pinfunction "20_20") (pintype "passive"))
      (node (ref "JTAG1") (pin "3") (pinfunction "3_3") (pintype "passive"))
      (node (ref "JTAG1") (pin "4") (pinfunction "4_4") (pintype "passive"))
      (node (ref "JTAG1") (pin "6") (pinfunction "6_6") (pintype "passive"))
      (node (ref "JTAG1") (pin "8") (pinfunction "8_8") (pintype "passive"))
      (node (ref "R1") (pin "2") (pinfunction "2_2") (pintype "passive"))
      (node (ref "R10") (pin "2") (pinfunction "2_2") (pintype "passive"))
      (node (ref "R15") (pin "2") (pinfunction "2_2") (pintype "passive"))
      (node (ref "R23") (pin "2") (pinfunction "2_2") (pintype "passive"))
      (node (ref "R4") (pin "2") (pinfunction "2_2") (pintype "passive"))
      (node (ref "R5") (pin "2") (pinfunction "2_2") (pintype "passive"))
      (node (ref "R6") (pin "2") (pinfunction "2_2") (pintype "passive"))
      (node (ref "R66") (pin "2") (pinfunction "2_2") (pintype "passive"))
      (node (ref "R69") (pin "2") (pinfunction "2_2") (pintype "passive"))
      (node (ref "R9") (pin "1") (pinfunction "1_1") (pintype "passive"))
      (node (ref "U$10") (pin "P$24") (pinfunction "VSS2_P$24") (pintype "bidirectional"))
      (node (ref "U$10") (pin "P$25") (pinfunction "VSS_P$25") (pintype "bidirectional"))
      (node (ref "U$10") (pin "P$26") (pinfunction "BM0_P$26") (pintype "bidirectional"))
      (node (ref "U$30") (pin "10") (pinfunction "GND_10") (pintype "bidirectional"))
      (node (ref "U$30") (pin "19") (pinfunction "GND_19") (pintype "bidirectional"))
      (node (ref "U$30") (pin "2") (pinfunction "A0_2") (pintype "bidirectional"))
      (node (ref "U$30") (pin "24") (pinfunction "GND_24") (pintype "bidirectional"))
      (node (ref "U$30") (pin "3") (pinfunction "A1_3") (pintype "bidirectional"))
      (node (ref "U$30") (pin "4") (pinfunction "A2_4") (pintype "bidirectional"))
      (node (ref "U$30") (pin "5") (pinfunction "A3_5") (pintype "bidirectional"))
      (node (ref "U$33") (pin "10") (pinfunction "GND_10") (pintype "bidirectional"))
      (node (ref "U$33") (pin "19") (pinfunction "GND_19") (pintype "bidirectional"))
      (node (ref "U$33") (pin "24") (pinfunction "GND_24") (pintype "bidirectional"))
      (node (ref "U$33") (pin "3") (pinfunction "A1_3") (pintype "bidirectional"))
      (node (ref "U$33") (pin "4") (pinfunction "A2_4") (pintype "bidirectional"))
      (node (ref "U$33") (pin "5") (pinfunction "A3_5") (pintype "bidirectional"))
      (node (ref "U$36") (pin "10") (pinfunction "GND_10") (pintype "bidirectional"))
      (node (ref "U$36") (pin "19") (pinfunction "GND_19") (pintype "bidirectional"))
      (node (ref "U$36") (pin "2") (pinfunction "A0_2") (pintype "bidirectional"))
      (node (ref "U$36") (pin "24") (pinfunction "GND_24") (pintype "bidirectional"))
      (node (ref "U$36") (pin "4") (pinfunction "A2_4") (pintype "bidirectional"))
      (node (ref "U$36") (pin "5") (pinfunction "A3_5") (pintype "bidirectional"))
      (node (ref "U$4") (pin "1") (pinfunction "EN_1") (pintype "bidirectional"))
      (node (ref "U$4") (pin "10") (pinfunction "GND_10") (pintype "power_in"))
      (node (ref "U$5") (pin "1") (pinfunction "EN_1") (pintype "bidirectional"))
      (node (ref "U$5") (pin "10") (pinfunction "GND_10") (pintype "power_in"))
      (node (ref "U$51") (pin "10") (pinfunction "GND_10") (pintype "bidirectional"))
      (node (ref "U$51") (pin "19") (pinfunction "GND_19") (pintype "bidirectional"))
      (node (ref "U$51") (pin "24") (pinfunction "GND_24") (pintype "bidirectional"))
      (node (ref "U$51") (pin "4") (pinfunction "A2_4") (pintype "bidirectional"))
      (node (ref "U$51") (pin "5") (pinfunction "A3_5") (pintype "bidirectional"))
      (node (ref "U$8") (pin "10") (pinfunction "GND_10") (pintype "bidirectional"))
      (node (ref "U$8") (pin "19") (pinfunction "GND_19") (pintype "bidirectional"))
      (node (ref "U$8") (pin "2") (pinfunction "A0_2") (pintype "bidirectional"))
      (node (ref "U$8") (pin "24") (pinfunction "GND_24") (pintype "bidirectional"))
      (node (ref "U$8") (pin "3") (pinfunction "A1_3") (pintype "bidirectional"))
      (node (ref "U$8") (pin "5") (pinfunction "A3_5") (pintype "bidirectional"))
      (node (ref "U1") (pin "2") (pinfunction "GND_2") (pintype "bidirectional"))
      (node (ref "U10") (pin "2") (pinfunction "GND_2") (pintype "passive"))
      (node (ref "U2") (pin "4") (pinfunction "G_4") (pintype "passive"))
      (node (ref "U3") (pin "7") (pinfunction "GND_7") (pintype "passive"))
      (node (ref "X2") (pin "10") (pinfunction "S_10") (pintype "passive"))
      (node (ref "X3") (pin "10") (pinfunction "S_10") (pintype "passive"))
      (node (ref "X6") (pin "14") (pinfunction "S_14") (pintype "passive"))
      (node (ref "X6") (pin "4") (pinfunction "S_4") (pintype "passive"))
    )
    (net (code "20") (name "JTAG_TCK") (class "Default")
      (node (ref "J1") (pin "84") (pinfunction "TCK_84") (pintype "bidirectional"))
      (node (ref "JTAG1") (pin "9") (pinfunction "9_9") (pintype "passive"))
    )
    (net (code "21") (name "JTAG_TDI") (class "Default")
      (node (ref "J1") (pin "86") (pinfunction "TDI_86") (pintype "bidirectional"))
      (node (ref "JTAG1") (pin "5") (pinfunction "5_5") (pintype "passive"))
    )
    (net (code "22") (name "JTAG_TDO") (class "Default")
      (node (ref "J1") (pin "88") (pinfunction "TDO_88") (pintype "bidirectional"))
      (node (ref "JTAG1") (pin "13") (pinfunction "13_13") (pintype "passive"))
    )
    (net (code "23") (name "JTAG_TMS") (class "Default")
      (node (ref "J1") (pin "82") (pinfunction "TMS_82") (pintype "bidirectional"))
      (node (ref "JTAG1") (pin "7") (pinfunction "7_7") (pintype "passive"))
    )
    (net (code "24") (name "LCD_CLOCK") (class "Default")
      (node (ref "J1") (pin "5") (pinfunction "PA5/AN5_5") (pintype "bidirectional"))
      (node (ref "U$10") (pin "P$32") (pinfunction "D0/SCK_P$32") (pintype "bidirectional"))
      (node (ref "X6") (pin "13") (pinfunction "S_13") (pintype "passive"))
    )
    (net (code "25") (name "LCD_CS") (class "Default")
      (node (ref "J1") (pin "13") (pinfunction "PC5/AN15_13") (pintype "bidirectional"))
      (node (ref "U$10") (pin "P$28") (pinfunction "CS0/A2_P$28") (pintype "bidirectional"))
    )
    (net (code "26") (name "LCD_DATA") (class "Default")
      (node (ref "J1") (pin "9") (pinfunction "PA7/AN7_9") (pintype "bidirectional"))
      (node (ref "U$10") (pin "P$31") (pinfunction "D3/SDA_P$31") (pintype "bidirectional"))
      (node (ref "X6") (pin "11") (pinfunction "S_11") (pintype "passive"))
    )
    (net (code "27") (name "LCD_PWR_SW") (class "Default")
      (node (ref "J1") (pin "41") (pinfunction "PB12_41") (pintype "bidirectional"))
      (node (ref "R3") (pin "2") (pinfunction "2_2") (pintype "passive"))
    )
    (net (code "28") (name "LCD_RESET") (class "Default")
      (node (ref "J1") (pin "15") (pinfunction "PB0/AN8_15") (pintype "bidirectional"))
      (node (ref "U$10") (pin "P$29") (pinfunction "RST_P$29") (pintype "bidirectional"))
    )
    (net (code "29") (name "MISO") (class "Default")
      (node (ref "X6") (pin "12") (pinfunction "S_12") (pintype "passive"))
    )
    (net (code "30") (name "Net-(C1-P$1)") (class "Default")
      (node (ref "C1") (pin "1") (pinfunction "P$1_1") (pintype "passive"))
      (node (ref "D1") (pin "C") (pinfunction "C_C") (pintype "passive"))
      (node (ref "U$10") (pin "P$1") (pinfunction "A1+_P$1") (pintype "bidirectional"))
    )
    (net (code "31") (name "Net-(C6-P$1)") (class "Default")
      (node (ref "C6") (pin "1") (pinfunction "P$1_1") (pintype "passive"))
      (node (ref "U$10") (pin "P$20") (pinfunction "VB1-_P$20") (pintype "bidirectional"))
    )
    (net (code "32") (name "Net-(C6-P$2)") (class "Default")
      (node (ref "C6") (pin "2") (pinfunction "P$2_2") (pintype "passive"))
      (node (ref "U$10") (pin "P$19") (pinfunction "VB1+_P$19") (pintype "bidirectional"))
    )
    (net (code "33") (name "Net-(C7-P$1)") (class "Default")
      (node (ref "C7") (pin "1") (pinfunction "P$1_1") (pintype "passive"))
      (node (ref "U$10") (pin "P$21") (pinfunction "VB0-_P$21") (pintype "bidirectional"))
    )
    (net (code "34") (name "Net-(C7-P$2)") (class "Default")
      (node (ref "C7") (pin "2") (pinfunction "P$2_2") (pintype "passive"))
      (node (ref "U$10") (pin "P$18") (pinfunction "VB0+_P$18") (pintype "bidirectional"))
    )
    (net (code "35") (name "Net-(C8-P$2)") (class "Default")
      (node (ref "C8") (pin "2") (pinfunction "P$2_2") (pintype "passive"))
      (node (ref "R9") (pin "2") (pinfunction "2_2") (pintype "passive"))
      (node (ref "U$10") (pin "P$17") (pinfunction "VLCD_P$17") (pintype "bidirectional"))
    )
    (net (code "36") (name "Net-(C11-P$1)") (class "Default")
      (node (ref "C11") (pin "1") (pinfunction "P$1_1") (pintype "passive"))
      (node (ref "R11") (pin "2") (pinfunction "2_2") (pintype "passive"))
      (node (ref "R26") (pin "1") (pinfunction "1_1") (pintype "passive"))
    )
    (net (code "37") (name "Net-(C26-P$1)") (class "Default")
      (node (ref "C26") (pin "1") (pinfunction "P$1_1") (pintype "passive"))
      (node (ref "U3") (pin "4") (pinfunction "SS_4") (pintype "input"))
    )
    (net (code "38") (name "Net-(C27-P$1)") (class "Default")
      (node (ref "C27") (pin "1") (pinfunction "P$1_1") (pintype "passive"))
      (node (ref "D2") (pin "C") (pinfunction "C_C") (pintype "passive"))
      (node (ref "L2") (pin "P$1") (pinfunction "1_P$1") (pintype "passive"))
      (node (ref "U3") (pin "8") (pinfunction "PH_8") (pintype "input"))
    )
    (net (code "39") (name "Net-(C27-P$2)") (class "Default")
      (node (ref "C27") (pin "2") (pinfunction "P$2_2") (pintype "passive"))
      (node (ref "U3") (pin "1") (pinfunction "BOOT_1") (pintype "input"))
    )
    (net (code "40") (name "Net-(C28-P$1)") (class "Default")
      (node (ref "C28") (pin "1") (pinfunction "P$1_1") (pintype "passive"))
      (node (ref "C29") (pin "1") (pinfunction "P$1_1") (pintype "passive"))
      (node (ref "U3") (pin "6") (pinfunction "COMP_6") (pintype "output"))
    )
    (net (code "41") (name "Net-(C28-P$2)") (class "Default")
      (node (ref "C28") (pin "2") (pinfunction "P$2_2") (pintype "passive"))
      (node (ref "R66") (pin "1") (pinfunction "1_1") (pintype "passive"))
    )
    (net (code "42") (name "Net-(LED1-BLUE)") (class "Default")
      (node (ref "LED1") (pin "3") (pinfunction "BLUE_3") (pintype "bidirectional"))
      (node (ref "U$30") (pin "8") (pinfunction "/OUT2_8") (pintype "bidirectional"))
    )
    (net (code "43") (name "Net-(LED1-GRN)") (class "Default")
      (node (ref "LED1") (pin "4") (pinfunction "GRN_4") (pintype "bidirectional"))
      (node (ref "U$30") (pin "7") (pinfunction "/OUT1_7") (pintype "bidirectional"))
    )
    (net (code "44") (name "Net-(LED1-RED)") (class "Default")
      (node (ref "LED1") (pin "1") (pinfunction "RED_1") (pintype "bidirectional"))
      (node (ref "U$30") (pin "6") (pinfunction "/OUT0_6") (pintype "bidirectional"))
    )
    (net (code "45") (name "Net-(LED2-BLUE)") (class "Default")
      (node (ref "LED2") (pin "3") (pinfunction "BLUE_3") (pintype "bidirectional"))
      (node (ref "U$30") (pin "12") (pinfunction "/OUT5_12") (pintype "bidirectional"))
    )
    (net (code "46") (name "Net-(LED2-GRN)") (class "Default")
      (node (ref "LED2") (pin "4") (pinfunction "GRN_4") (pintype "bidirectional"))
      (node (ref "U$30") (pin "11") (pinfunction "/OUT4_11") (pintype "bidirectional"))
    )
    (net (code "47") (name "Net-(LED2-RED)") (class "Default")
      (node (ref "LED2") (pin "1") (pinfunction "RED_1") (pintype "bidirectional"))
      (node (ref "U$30") (pin "9") (pinfunction "/OUT3_9") (pintype "bidirectional"))
    )
    (net (code "48") (name "Net-(LED3-BLUE)") (class "Default")
      (node (ref "LED3") (pin "3") (pinfunction "BLUE_3") (pintype "bidirectional"))
      (node (ref "U$30") (pin "15") (pinfunction "/OUT8_15") (pintype "bidirectional"))
    )
    (net (code "49") (name "Net-(LED3-GRN)") (class "Default")
      (node (ref "LED3") (pin "4") (pinfunction "GRN_4") (pintype "bidirectional"))
      (node (ref "U$30") (pin "14") (pinfunction "/OUT7_14") (pintype "bidirectional"))
    )
    (net (code "50") (name "Net-(LED3-RED)") (class "Default")
      (node (ref "LED3") (pin "1") (pinfunction "RED_1") (pintype "bidirectional"))
      (node (ref "U$30") (pin "13") (pinfunction "/OUT6_13") (pintype "bidirectional"))
    )
    (net (code "51") (name "Net-(LED4-BLUE)") (class "Default")
      (node (ref "LED4") (pin "3") (pinfunction "BLUE_3") (pintype "bidirectional"))
      (node (ref "U$30") (pin "18") (pinfunction "/OUT11_18") (pintype "bidirectional"))
    )
    (net (code "52") (name "Net-(LED4-GRN)") (class "Default")
      (node (ref "LED4") (pin "4") (pinfunction "GRN_4") (pintype "bidirectional"))
      (node (ref "U$30") (pin "17") (pinfunction "/OUT10_17") (pintype "bidirectional"))
    )
    (net (code "53") (name "Net-(LED4-RED)") (class "Default")
      (node (ref "LED4") (pin "1") (pinfunction "RED_1") (pintype "bidirectional"))
      (node (ref "U$30") (pin "16") (pinfunction "/OUT9_16") (pintype "bidirectional"))
    )
    (net (code "54") (name "Net-(LED5-BLUE)") (class "Default")
      (node (ref "LED5") (pin "3") (pinfunction "BLUE_3") (pintype "bidirectional"))
      (node (ref "U$30") (pin "22") (pinfunction "/OUT14_22") (pintype "bidirectional"))
    )
    (net (code "55") (name "Net-(LED5-GRN)") (class "Default")
      (node (ref "LED5") (pin "4") (pinfunction "GRN_4") (pintype "bidirectional"))
      (node (ref "U$30") (pin "21") (pinfunction "/OUT13_21") (pintype "bidirectional"))
    )
    (net (code "56") (name "Net-(LED5-RED)") (class "Default")
      (node (ref "LED5") (pin "1") (pinfunction "RED_1") (pintype "bidirectional"))
      (node (ref "U$30") (pin "20") (pinfunction "/OUT12_20") (pintype "bidirectional"))
    )
    (net (code "57") (name "Net-(LED6-BLUE)") (class "Default")
      (node (ref "LED6") (pin "3") (pinfunction "BLUE_3") (pintype "bidirectional"))
      (node (ref "U$33") (pin "8") (pinfunction "/OUT2_8") (pintype "bidirectional"))
    )
    (net (code "58") (name "Net-(LED6-GRN)") (class "Default")
      (node (ref "LED6") (pin "4") (pinfunction "GRN_4") (pintype "bidirectional"))
      (node (ref "U$33") (pin "7") (pinfunction "/OUT1_7") (pintype "bidirectional"))
    )
    (net (code "59") (name "Net-(LED6-RED)") (class "Default")
      (node (ref "LED6") (pin "1") (pinfunction "RED_1") (pintype "bidirectional"))
      (node (ref "U$33") (pin "6") (pinfunction "/OUT0_6") (pintype "bidirectional"))
    )
    (net (code "60") (name "Net-(LED7-BLUE)") (class "Default")
      (node (ref "LED7") (pin "3") (pinfunction "BLUE_3") (pintype "bidirectional"))
      (node (ref "U$33") (pin "12") (pinfunction "/OUT5_12") (pintype "bidirectional"))
    )
    (net (code "61") (name "Net-(LED7-GRN)") (class "Default")
      (node (ref "LED7") (pin "4") (pinfunction "GRN_4") (pintype "bidirectional"))
      (node (ref "U$33") (pin "11") (pinfunction "/OUT4_11") (pintype "bidirectional"))
    )
    (net (code "62") (name "Net-(LED7-RED)") (class "Default")
      (node (ref "LED7") (pin "1") (pinfunction "RED_1") (pintype "bidirectional"))
      (node (ref "U$33") (pin "9") (pinfunction "/OUT3_9") (pintype "bidirectional"))
    )
    (net (code "63") (name "Net-(LED8-BLUE)") (class "Default")
      (node (ref "LED8") (pin "3") (pinfunction "BLUE_3") (pintype "bidirectional"))
      (node (ref "U$33") (pin "15") (pinfunction "/OUT8_15") (pintype "bidirectional"))
    )
    (net (code "64") (name "Net-(LED8-GRN)") (class "Default")
      (node (ref "LED8") (pin "4") (pinfunction "GRN_4") (pintype "bidirectional"))
      (node (ref "U$33") (pin "14") (pinfunction "/OUT7_14") (pintype "bidirectional"))
    )
    (net (code "65") (name "Net-(LED8-RED)") (class "Default")
      (node (ref "LED8") (pin "1") (pinfunction "RED_1") (pintype "bidirectional"))
      (node (ref "U$33") (pin "13") (pinfunction "/OUT6_13") (pintype "bidirectional"))
    )
    (net (code "66") (name "Net-(LED9-BLUE)") (class "Default")
      (node (ref "LED9") (pin "3") (pinfunction "BLUE_3") (pintype "bidirectional"))
      (node (ref "U$33") (pin "18") (pinfunction "/OUT11_18") (pintype "bidirectional"))
    )
    (net (code "67") (name "Net-(LED9-GRN)") (class "Default")
      (node (ref "LED9") (pin "4") (pinfunction "GRN_4") (pintype "bidirectional"))
      (node (ref "U$33") (pin "17") (pinfunction "/OUT10_17") (pintype "bidirectional"))
    )
    (net (code "68") (name "Net-(LED9-RED)") (class "Default")
      (node (ref "LED9") (pin "1") (pinfunction "RED_1") (pintype "bidirectional"))
      (node (ref "U$33") (pin "16") (pinfunction "/OUT9_16") (pintype "bidirectional"))
    )
    (net (code "69") (name "Net-(LED10-BLUE)") (class "Default")
      (node (ref "LED10") (pin "3") (pinfunction "BLUE_3") (pintype "bidirectional"))
      (node (ref "U$33") (pin "22") (pinfunction "/OUT14_22") (pintype "bidirectional"))
    )
    (net (code "70") (name "Net-(LED10-GRN)") (class "Default")
      (node (ref "LED10") (pin "4") (pinfunction "GRN_4") (pintype "bidirectional"))
      (node (ref "U$33") (pin "21") (pinfunction "/OUT13_21") (pintype "bidirectional"))
    )
    (net (code "71") (name "Net-(LED10-RED)") (class "Default")
      (node (ref "LED10") (pin "1") (pinfunction "RED_1") (pintype "bidirectional"))
      (node (ref "U$33") (pin "20") (pinfunction "/OUT12_20") (pintype "bidirectional"))
    )
    (net (code "72") (name "Net-(LED11-BLUE)") (class "Default")
      (node (ref "LED11") (pin "3") (pinfunction "BLUE_3") (pintype "bidirectional"))
      (node (ref "U$36") (pin "8") (pinfunction "/OUT2_8") (pintype "bidirectional"))
    )
    (net (code "73") (name "Net-(LED11-GRN)") (class "Default")
      (node (ref "LED11") (pin "4") (pinfunction "GRN_4") (pintype "bidirectional"))
      (node (ref "U$36") (pin "7") (pinfunction "/OUT1_7") (pintype "bidirectional"))
    )
    (net (code "74") (name "Net-(LED11-RED)") (class "Default")
      (node (ref "LED11") (pin "1") (pinfunction "RED_1") (pintype "bidirectional"))
      (node (ref "U$36") (pin "6") (pinfunction "/OUT0_6") (pintype "bidirectional"))
    )
    (net (code "75") (name "Net-(LED12-BLUE)") (class "Default")
      (node (ref "LED12") (pin "3") (pinfunction "BLUE_3") (pintype "bidirectional"))
      (node (ref "U$36") (pin "12") (pinfunction "/OUT5_12") (pintype "bidirectional"))
    )
    (net (code "76") (name "Net-(LED12-GRN)") (class "Default")
      (node (ref "LED12") (pin "4") (pinfunction "GRN_4") (pintype "bidirectional"))
      (node (ref "U$36") (pin "11") (pinfunction "/OUT4_11") (pintype "bidirectional"))
    )
    (net (code "77") (name "Net-(LED12-RED)") (class "Default")
      (node (ref "LED12") (pin "1") (pinfunction "RED_1") (pintype "bidirectional"))
      (node (ref "U$36") (pin "9") (pinfunction "/OUT3_9") (pintype "bidirectional"))
    )
    (net (code "78") (name "Net-(LED13-BLUE)") (class "Default")
      (node (ref "LED13") (pin "3") (pinfunction "BLUE_3") (pintype "bidirectional"))
      (node (ref "U$36") (pin "15") (pinfunction "/OUT8_15") (pintype "bidirectional"))
    )
    (net (code "79") (name "Net-(LED13-GRN)") (class "Default")
      (node (ref "LED13") (pin "4") (pinfunction "GRN_4") (pintype "bidirectional"))
      (node (ref "U$36") (pin "14") (pinfunction "/OUT7_14") (pintype "bidirectional"))
    )
    (net (code "80") (name "Net-(LED13-RED)") (class "Default")
      (node (ref "LED13") (pin "1") (pinfunction "RED_1") (pintype "bidirectional"))
      (node (ref "U$36") (pin "13") (pinfunction "/OUT6_13") (pintype "bidirectional"))
    )
    (net (code "81") (name "Net-(LED14-BLUE)") (class "Default")
      (node (ref "LED14") (pin "3") (pinfunction "BLUE_3") (pintype "bidirectional"))
      (node (ref "U$36") (pin "18") (pinfunction "/OUT11_18") (pintype "bidirectional"))
    )
    (net (code "82") (name "Net-(LED14-GRN)") (class "Default")
      (node (ref "LED14") (pin "4") (pinfunction "GRN_4") (pintype "bidirectional"))
      (node (ref "U$36") (pin "17") (pinfunction "/OUT10_17") (pintype "bidirectional"))
    )
    (net (code "83") (name "Net-(LED14-RED)") (class "Default")
      (node (ref "LED14") (pin "1") (pinfunction "RED_1") (pintype "bidirectional"))
      (node (ref "U$36") (pin "16") (pinfunction "/OUT9_16") (pintype "bidirectional"))
    )
    (net (code "84") (name "Net-(LED15-BLUE)") (class "Default")
      (node (ref "LED15") (pin "3") (pinfunction "BLUE_3") (pintype "bidirectional"))
      (node (ref "U$36") (pin "22") (pinfunction "/OUT14_22") (pintype "bidirectional"))
    )
    (net (code "85") (name "Net-(LED15-GRN)") (class "Default")
      (node (ref "LED15") (pin "4") (pinfunction "GRN_4") (pintype "bidirectional"))
      (node (ref "U$36") (pin "21") (pinfunction "/OUT13_21") (pintype "bidirectional"))
    )
    (net (code "86") (name "Net-(LED15-RED)") (class "Default")
      (node (ref "LED15") (pin "1") (pinfunction "RED_1") (pintype "bidirectional"))
      (node (ref "U$36") (pin "20") (pinfunction "/OUT12_20") (pintype "bidirectional"))
    )
    (net (code "87") (name "Net-(LED16-BLUE)") (class "Default")
      (node (ref "LED16") (pin "3") (pinfunction "BLUE_3") (pintype "bidirectional"))
      (node (ref "U$51") (pin "8") (pinfunction "/OUT2_8") (pintype "bidirectional"))
    )
    (net (code "88") (name "Net-(LED16-GRN)") (class "Default")
      (node (ref "LED16") (pin "4") (pinfunction "GRN_4") (pintype "bidirectional"))
      (node (ref "U$51") (pin "7") (pinfunction "/OUT1_7") (pintype "bidirectional"))
    )
    (net (code "89") (name "Net-(LED16-RED)") (class "Default")
      (node (ref "LED16") (pin "1") (pinfunction "RED_1") (pintype "bidirectional"))
      (node (ref "U$51") (pin "6") (pinfunction "/OUT0_6") (pintype "bidirectional"))
    )
    (net (code "90") (name "Net-(LED17-BLUE)") (class "Default")
      (node (ref "LED17") (pin "3") (pinfunction "BLUE_3") (pintype "bidirectional"))
      (node (ref "U$51") (pin "12") (pinfunction "/OUT5_12") (pintype "bidirectional"))
    )
    (net (code "91") (name "Net-(LED17-GRN)") (class "Default")
      (node (ref "LED17") (pin "4") (pinfunction "GRN_4") (pintype "bidirectional"))
      (node (ref "U$51") (pin "11") (pinfunction "/OUT4_11") (pintype "bidirectional"))
    )
    (net (code "92") (name "Net-(LED17-RED)") (class "Default")
      (node (ref "LED17") (pin "1") (pinfunction "RED_1") (pintype "bidirectional"))
      (node (ref "U$51") (pin "9") (pinfunction "/OUT3_9") (pintype "bidirectional"))
    )
    (net (code "93") (name "Net-(LED18-BLUE)") (class "Default")
      (node (ref "LED18") (pin "3") (pinfunction "BLUE_3") (pintype "bidirectional"))
      (node (ref "U$51") (pin "15") (pinfunction "/OUT8_15") (pintype "bidirectional"))
    )
    (net (code "94") (name "Net-(LED18-GRN)") (class "Default")
      (node (ref "LED18") (pin "4") (pinfunction "GRN_4") (pintype "bidirectional"))
      (node (ref "U$51") (pin "14") (pinfunction "/OUT7_14") (pintype "bidirectional"))
    )
    (net (code "95") (name "Net-(LED18-RED)") (class "Default")
      (node (ref "LED18") (pin "1") (pinfunction "RED_1") (pintype "bidirectional"))
      (node (ref "U$51") (pin "13") (pinfunction "/OUT6_13") (pintype "bidirectional"))
    )
    (net (code "96") (name "Net-(LED19-BLUE)") (class "Default")
      (node (ref "LED19") (pin "3") (pinfunction "BLUE_3") (pintype "bidirectional"))
      (node (ref "U$51") (pin "18") (pinfunction "/OUT11_18") (pintype "bidirectional"))
    )
    (net (code "97") (name "Net-(LED19-GRN)") (class "Default")
      (node (ref "LED19") (pin "4") (pinfunction "GRN_4") (pintype "bidirectional"))
      (node (ref "U$51") (pin "17") (pinfunction "/OUT10_17") (pintype "bidirectional"))
    )
    (net (code "98") (name "Net-(LED19-RED)") (class "Default")
      (node (ref "LED19") (pin "1") (pinfunction "RED_1") (pintype "bidirectional"))
      (node (ref "U$51") (pin "16") (pinfunction "/OUT9_16") (pintype "bidirectional"))
    )
    (net (code "99") (name "Net-(LED20-BLUE)") (class "Default")
      (node (ref "LED20") (pin "3") (pinfunction "BLUE_3") (pintype "bidirectional"))
      (node (ref "U$51") (pin "22") (pinfunction "/OUT14_22") (pintype "bidirectional"))
    )
    (net (code "100") (name "Net-(LED20-GRN)") (class "Default")
      (node (ref "LED20") (pin "4") (pinfunction "GRN_4") (pintype "bidirectional"))
      (node (ref "U$51") (pin "21") (pinfunction "/OUT13_21") (pintype "bidirectional"))
    )
    (net (code "101") (name "Net-(LED20-RED)") (class "Default")
      (node (ref "LED20") (pin "1") (pinfunction "RED_1") (pintype "bidirectional"))
      (node (ref "U$51") (pin "20") (pinfunction "/OUT12_20") (pintype "bidirectional"))
    )
    (net (code "102") (name "Net-(LED21-BLUE)") (class "Default")
      (node (ref "LED21") (pin "3") (pinfunction "BLUE_3") (pintype "bidirectional"))
      (node (ref "U$8") (pin "8") (pinfunction "/OUT2_8") (pintype "bidirectional"))
    )
    (net (code "103") (name "Net-(LED21-GRN)") (class "Default")
      (node (ref "LED21") (pin "4") (pinfunction "GRN_4") (pintype "bidirectional"))
      (node (ref "U$8") (pin "7") (pinfunction "/OUT1_7") (pintype "bidirectional"))
    )
    (net (code "104") (name "Net-(LED21-RED)") (class "Default")
      (node (ref "LED21") (pin "1") (pinfunction "RED_1") (pintype "bidirectional"))
      (node (ref "U$8") (pin "6") (pinfunction "/OUT0_6") (pintype "bidirectional"))
    )
    (net (code "105") (name "Net-(LED22-BLUE)") (class "Default")
      (node (ref "LED22") (pin "3") (pinfunction "BLUE_3") (pintype "bidirectional"))
      (node (ref "U$8") (pin "12") (pinfunction "/OUT5_12") (pintype "bidirectional"))
    )
    (net (code "106") (name "Net-(LED22-GRN)") (class "Default")
      (node (ref "LED22") (pin "4") (pinfunction "GRN_4") (pintype "bidirectional"))
      (node (ref "U$8") (pin "11") (pinfunction "/OUT4_11") (pintype "bidirectional"))
    )
    (net (code "107") (name "Net-(LED22-RED)") (class "Default")
      (node (ref "LED22") (pin "1") (pinfunction "RED_1") (pintype "bidirectional"))
      (node (ref "U$8") (pin "9") (pinfunction "/OUT3_9") (pintype "bidirectional"))
    )
    (net (code "108") (name "Net-(LED23-BLUE)") (class "Default")
      (node (ref "LED23") (pin "3") (pinfunction "BLUE_3") (pintype "bidirectional"))
      (node (ref "U$8") (pin "15") (pinfunction "/OUT8_15") (pintype "bidirectional"))
    )
    (net (code "109") (name "Net-(LED23-GRN)") (class "Default")
      (node (ref "LED23") (pin "4") (pinfunction "GRN_4") (pintype "bidirectional"))
      (node (ref "U$8") (pin "14") (pinfunction "/OUT7_14") (pintype "bidirectional"))
    )
    (net (code "110") (name "Net-(LED23-RED)") (class "Default")
      (node (ref "LED23") (pin "1") (pinfunction "RED_1") (pintype "bidirectional"))
      (node (ref "U$8") (pin "13") (pinfunction "/OUT6_13") (pintype "bidirectional"))
    )
    (net (code "111") (name "Net-(LED24-BLUE)") (class "Default")
      (node (ref "LED24") (pin "3") (pinfunction "BLUE_3") (pintype "bidirectional"))
      (node (ref "U$8") (pin "18") (pinfunction "/OUT11_18") (pintype "bidirectional"))
    )
    (net (code "112") (name "Net-(LED24-GRN)") (class "Default")
      (node (ref "LED24") (pin "4") (pinfunction "GRN_4") (pintype "bidirectional"))
      (node (ref "U$8") (pin "17") (pinfunction "/OUT10_17") (pintype "bidirectional"))
    )
    (net (code "113") (name "Net-(LED24-RED)") (class "Default")
      (node (ref "LED24") (pin "1") (pinfunction "RED_1") (pintype "bidirectional"))
      (node (ref "U$8") (pin "16") (pinfunction "/OUT9_16") (pintype "bidirectional"))
    )
    (net (code "114") (name "Net-(LED25-BLUE)") (class "Default")
      (node (ref "LED25") (pin "3") (pinfunction "BLUE_3") (pintype "bidirectional"))
      (node (ref "U$8") (pin "22") (pinfunction "/OUT14_22") (pintype "bidirectional"))
    )
    (net (code "115") (name "Net-(LED25-GRN)") (class "Default")
      (node (ref "LED25") (pin "4") (pinfunction "GRN_4") (pintype "bidirectional"))
      (node (ref "U$8") (pin "21") (pinfunction "/OUT13_21") (pintype "bidirectional"))
    )
    (net (code "116") (name "Net-(LED25-RED)") (class "Default")
      (node (ref "LED25") (pin "1") (pinfunction "RED_1") (pintype "bidirectional"))
      (node (ref "U$8") (pin "20") (pinfunction "/OUT12_20") (pintype "bidirectional"))
    )
    (net (code "117") (name "Net-(PTC2-2)") (class "Default")
      (node (ref "PTC2") (pin "P$2") (pinfunction "2_P$2") (pintype "passive"))
      (node (ref "U2") (pin "1") (pinfunction "S_2_1") (pintype "passive"))
      (node (ref "U2") (pin "2") (pinfunction "S_2") (pintype "passive"))
      (node (ref "U2") (pin "3") (pinfunction "S_3_3") (pintype "passive"))
    )
    (net (code "118") (name "Net-(Q2-D)") (class "Default")
      (node (ref "Q2") (pin "3") (pinfunction "D_3") (pintype "passive"))
      (node (ref "U$10") (pin "P$22") (pinfunction "VDD_P$22") (pintype "bidirectional"))
      (node (ref "U$10") (pin "P$23") (pinfunction "VDD2/3_P$23") (pintype "bidirectional"))
      (node (ref "U$10") (pin "P$30") (pinfunction "D6_P$30") (pintype "bidirectional"))
    )
    (net (code "119") (name "Net-(Q2-G)") (class "Default")
      (node (ref "Q2") (pin "1") (pinfunction "G_1") (pintype "passive"))
      (node (ref "R2") (pin "2") (pinfunction "2_2") (pintype "passive"))
      (node (ref "R3") (pin "1") (pinfunction "1_1") (pintype "passive"))
    )
    (net (code "120") (name "Net-(SW1-S1)") (class "Default")
      (node (ref "R11") (pin "1") (pinfunction "1_1") (pintype "passive"))
      (node (ref "SW1") (pin "P$3") (pinfunction "S1_P$3") (pintype "passive"))
    )
    (net (code "121") (name "Net-(SW1-S2)") (class "Default")
      (node (ref "R26") (pin "2") (pinfunction "2_2") (pintype "passive"))
      (node (ref "SW1") (pin "P$4") (pinfunction "S2_P$4") (pintype "passive"))
    )
    (net (code "122") (name "Net-(U$4-IN1)") (class "Default")
      (node (ref "U$4") (pin "2") (pinfunction "IN1_2") (pintype "bidirectional"))
      (node (ref "X2") (pin "2") (pinfunction "S_2") (pintype "passive"))
    )
    (net (code "123") (name "Net-(U$4-IN2)") (class "Default")
      (node (ref "U$4") (pin "3") (pinfunction "IN2_3") (pintype "bidirectional"))
      (node (ref "X2") (pin "3") (pinfunction "S_3") (pintype "passive"))
    )
    (net (code "124") (name "Net-(U$4-IN3)") (class "Default")
      (node (ref "U$4") (pin "4") (pinfunction "IN3_4") (pintype "bidirectional"))
      (node (ref "X2") (pin "4") (pinfunction "S_4") (pintype "passive"))
    )
    (net (code "125") (name "Net-(U$4-IN4)") (class "Default")
      (node (ref "U$4") (pin "5") (pinfunction "IN4_5") (pintype "bidirectional"))
      (node (ref "X2") (pin "5") (pinfunction "S_5") (pintype "passive"))
    )
    (net (code "126") (name "Net-(U$4-IN5)") (class "Default")
      (node (ref "U$4") (pin "6") (pinfunction "IN5_6") (pintype "bidirectional"))
      (node (ref "X2") (pin "6") (pinfunction "S_6") (pintype "passive"))
    )
    (net (code "127") (name "Net-(U$5-IN2)") (class "Default")
      (node (ref "U$5") (pin "3") (pinfunction "IN2_3") (pintype "bidirectional"))
      (node (ref "X3") (pin "3") (pinfunction "S_3") (pintype "passive"))
    )
    (net (code "128") (name "Net-(U$5-IN3)") (class "Default")
      (node (ref "U$5") (pin "4") (pinfunction "IN3_4") (pintype "bidirectional"))
      (node (ref "X3") (pin "4") (pinfunction "S_4") (pintype "passive"))
    )
    (net (code "129") (name "Net-(U$5-IN4)") (class "Default")
      (node (ref "U$5") (pin "5") (pinfunction "IN4_5") (pintype "bidirectional"))
      (node (ref "X3") (pin "5") (pinfunction "S_5") (pintype "passive"))
    )
    (net (code "130") (name "Net-(U$5-IN5)") (class "Default")
      (node (ref "U$5") (pin "6") (pinfunction "IN5_6") (pintype "bidirectional"))
      (node (ref "X3") (pin "6") (pinfunction "S_6") (pintype "passive"))
    )
    (net (code "131") (name "Net-(U$5-IN6)") (class "Default")
      (node (ref "U$5") (pin "7") (pinfunction "IN6_7") (pintype "bidirectional"))
      (node (ref "X3") (pin "7") (pinfunction "S_7") (pintype "passive"))
    )
    (net (code "132") (name "Net-(U$5-IN7)") (class "Default")
      (node (ref "U$5") (pin "8") (pinfunction "IN7_8") (pintype "bidirectional"))
      (node (ref "X3") (pin "8") (pinfunction "S_8") (pintype "passive"))
    )
    (net (code "133") (name "Net-(U$5-IN8)") (class "Default")
      (node (ref "U$5") (pin "9") (pinfunction "IN8_9") (pintype "bidirectional"))
      (node (ref "X3") (pin "9") (pinfunction "S_9") (pintype "passive"))
    )
    (net (code "134") (name "Net-(U$8-REXT)") (class "Default")
      (node (ref "R10") (pin "1") (pinfunction "1_1") (pintype "passive"))
      (node (ref "U$8") (pin "1") (pinfunction "REXT_1") (pintype "bidirectional"))
    )
    (net (code "135") (name "Net-(U$10-A2+)") (class "Default")
      (node (ref "U$10") (pin "P$14") (pinfunction "C1-_P$14") (pintype "bidirectional"))
      (node (ref "U$10") (pin "P$2") (pinfunction "A2+_P$2") (pintype "bidirectional"))
    )
    (net (code "136") (name "Net-(U$10-A3+)") (class "Default")
      (node (ref "U$10") (pin "P$15") (pinfunction "C2-_P$15") (pintype "bidirectional"))
      (node (ref "U$10") (pin "P$3") (pinfunction "A3+_P$3") (pintype "bidirectional"))
    )
    (net (code "137") (name "Net-(U$10-C3-)") (class "Default")
      (node (ref "R1") (pin "1") (pinfunction "1_1") (pintype "passive"))
      (node (ref "U$10") (pin "P$16") (pinfunction "C3-_P$16") (pintype "bidirectional"))
      (node (ref "U1") (pin "3") (pinfunction "FB_3") (pintype "bidirectional"))
    )
    (net (code "138") (name "Net-(U$30-REXT)") (class "Default")
      (node (ref "R4") (pin "1") (pinfunction "1_1") (pintype "passive"))
      (node (ref "U$30") (pin "1") (pinfunction "REXT_1") (pintype "bidirectional"))
    )
    (net (code "139") (name "Net-(U$33-REXT)") (class "Default")
      (node (ref "R5") (pin "1") (pinfunction "1_1") (pintype "passive"))
      (node (ref "U$33") (pin "1") (pinfunction "REXT_1") (pintype "bidirectional"))
    )
    (net (code "140") (name "Net-(U$36-REXT)") (class "Default")
      (node (ref "R6") (pin "1") (pinfunction "1_1") (pintype "passive"))
      (node (ref "U$36") (pin "1") (pinfunction "REXT_1") (pintype "bidirectional"))
    )
    (net (code "141") (name "Net-(U$51-REXT)") (class "Default")
      (node (ref "R15") (pin "1") (pinfunction "1_1") (pintype "passive"))
      (node (ref "U$51") (pin "1") (pinfunction "REXT_1") (pintype "bidirectional"))
    )
    (net (code "142") (name "Net-(U1-SW)") (class "Default")
      (node (ref "D1") (pin "A") (pinfunction "A_A") (pintype "passive"))
      (node (ref "L1") (pin "1") (pinfunction "1_1") (pintype "passive"))
      (node (ref "U1") (pin "1") (pinfunction "SW_1") (pintype "bidirectional"))
    )
    (net (code "143") (name "Net-(U3-EN)") (class "Default")
      (node (ref "R22") (pin "2") (pinfunction "2_2") (pintype "passive"))
      (node (ref "R23") (pin "1") (pinfunction "1_1") (pintype "passive"))
      (node (ref "U3") (pin "3") (pinfunction "EN_3") (pintype "input"))
    )
    (net (code "144") (name "Net-(U3-VSENSE)") (class "Default")
      (node (ref "R68") (pin "2") (pinfunction "2_2") (pintype "passive"))
      (node (ref "R69") (pin "1") (pinfunction "1_1") (pintype "passive"))
      (node (ref "U3") (pin "5") (pinfunction "VSENSE_5") (pintype "input"))
    )
    (net (code "145") (name "RESET") (class "Default")
      (node (ref "J1") (pin "90") (pinfunction "RESET_90") (pintype "bidirectional"))
      (node (ref "JTAG1") (pin "15") (pinfunction "15_15") (pintype "passive"))
    )
    (net (code "146") (name "SCL") (class "Default")
      (node (ref "J1") (pin "37") (pinfunction "PB10_37") (pintype "bidirectional"))
      (node (ref "R8") (pin "1") (pinfunction "1_1") (pintype "passive"))
      (node (ref "U$30") (pin "26") (pinfunction "SCL_26") (pintype "bidirectional"))
      (node (ref "U$33") (pin "26") (pinfunction "SCL_26") (pintype "bidirectional"))
      (node (ref "U$36") (pin "26") (pinfunction "SCL_26") (pintype "bidirectional"))
      (node (ref "U$51") (pin "26") (pinfunction "SCL_26") (pintype "bidirectional"))
      (node (ref "U$8") (pin "26") (pinfunction "SCL_26") (pintype "bidirectional"))
      (node (ref "X6") (pin "10") (pinfunction "S_10") (pintype "passive"))
    )
    (net (code "147") (name "SDA") (class "Default")
      (node (ref "J1") (pin "39") (pinfunction "PB11_39") (pintype "bidirectional"))
      (node (ref "R7") (pin "1") (pinfunction "1_1") (pintype "passive"))
      (node (ref "U$30") (pin "27") (pinfunction "SDA_27") (pintype "bidirectional"))
      (node (ref "U$33") (pin "27") (pinfunction "SDA_27") (pintype "bidirectional"))
      (node (ref "U$36") (pin "27") (pinfunction "SDA_27") (pintype "bidirectional"))
      (node (ref "U$51") (pin "27") (pinfunction "SDA_27") (pintype "bidirectional"))
      (node (ref "U$8") (pin "27") (pinfunction "SDA_27") (pintype "bidirectional"))
      (node (ref "X6") (pin "9") (pinfunction "S_9") (pintype "passive"))
    )
    (net (code "148") (name "SW1") (class "Default")
      (node (ref "J1") (pin "17") (pinfunction "PB1/AN9_17") (pintype "bidirectional"))
      (node (ref "X3") (pin "2") (pinfunction "S_2") (pintype "passive"))
    )
    (net (code "149") (name "SW2") (class "Default")
      (node (ref "J1") (pin "19") (pinfunction "PE7_19") (pintype "bidirectional"))
      (node (ref "U$5") (pin "18") (pinfunction "OUT2_18") (pintype "bidirectional"))
    )
    (net (code "150") (name "SW3") (class "Default")
      (node (ref "J1") (pin "21") (pinfunction "PE8_21") (pintype "bidirectional"))
      (node (ref "U$5") (pin "17") (pinfunction "OUT3_17") (pintype "bidirectional"))
    )
    (net (code "151") (name "SW4") (class "Default")
      (node (ref "J1") (pin "23") (pinfunction "PE9_23") (pintype "bidirectional"))
      (node (ref "U$5") (pin "16") (pinfunction "OUT4_16") (pintype "bidirectional"))
    )
    (net (code "152") (name "SW5") (class "Default")
      (node (ref "J1") (pin "25") (pinfunction "PE10_25") (pintype "bidirectional"))
      (node (ref "U$5") (pin "15") (pinfunction "OUT5_15") (pintype "bidirectional"))
    )
    (net (code "153") (name "SW6") (class "Default")
      (node (ref "J1") (pin "27") (pinfunction "PE11_27") (pintype "bidirectional"))
      (node (ref "U$5") (pin "14") (pinfunction "OUT6_14") (pintype "bidirectional"))
    )
    (net (code "154") (name "SW7") (class "Default")
      (node (ref "J1") (pin "29") (pinfunction "PE12_29") (pintype "bidirectional"))
      (node (ref "U$5") (pin "13") (pinfunction "OUT7_13") (pintype "bidirectional"))
    )
    (net (code "155") (name "SW8") (class "Default")
      (node (ref "J1") (pin "31") (pinfunction "PE13_31") (pintype "bidirectional"))
      (node (ref "U$5") (pin "12") (pinfunction "OUT8_12") (pintype "bidirectional"))
    )
    (net (code "156") (name "VCC") (class "Default")
      (node (ref "CN1") (pin "1") (pinfunction "1_1") (pintype "passive"))
      (node (ref "U2") (pin "5") (pinfunction "D_4_5") (pintype "passive"))
      (node (ref "U2") (pin "6") (pinfunction "D_6") (pintype "passive"))
      (node (ref "U2") (pin "7") (pinfunction "D_2_7") (pintype "passive"))
      (node (ref "U2") (pin "8") (pinfunction "D_3_8") (pintype "passive"))
      (node (ref "X6") (pin "3") (pinfunction "S_3") (pintype "passive"))
    )
    (net (code "157") (name "unconnected-(J1A-D+-Pad76)") (class "Default")
      (node (ref "J1") (pin "76") (pinfunction "D+_76") (pintype "bidirectional"))
    )
    (net (code "158") (name "unconnected-(J1A-D--Pad74)") (class "Default")
      (node (ref "J1") (pin "74") (pinfunction "D-_74") (pintype "bidirectional"))
    )
    (net (code "159") (name "unconnected-(J1A-ID-Pad72)") (class "Default")
      (node (ref "J1") (pin "72") (pinfunction "ID_72") (pintype "bidirectional"))
    )
    (net (code "160") (name "unconnected-(J1B-PA4{slash}AN4-Pad3)") (class "Default")
      (node (ref "J1") (pin "3") (pinfunction "PA4/AN4_3") (pintype "bidirectional"))
    )
    (net (code "161") (name "unconnected-(J1B-PA6{slash}AN6-Pad7)") (class "Default")
      (node (ref "J1") (pin "7") (pinfunction "PA6/AN6_7") (pintype "bidirectional"))
    )
    (net (code "162") (name "unconnected-(J1B-PE14-Pad33)") (class "Default")
      (node (ref "J1") (pin "33") (pinfunction "PE14_33") (pintype "bidirectional"))
    )
    (net (code "163") (name "unconnected-(J1B-PE15-Pad35)") (class "Default")
      (node (ref "J1") (pin "35") (pinfunction "PE15_35") (pintype "bidirectional"))
    )
    (net (code "164") (name "unconnected-(J1C-PA8-Pad73)") (class "Default")
      (node (ref "J1") (pin "73") (pinfunction "PA8_73") (pintype "bidirectional"))
    )
    (net (code "165") (name "unconnected-(J1C-PA9-Pad75)") (class "Default")
      (node (ref "J1") (pin "75") (pinfunction "PA9_75") (pintype "bidirectional"))
    )
    (net (code "166") (name "unconnected-(J1C-PB13-Pad43)") (class "Default")
      (node (ref "J1") (pin "43") (pinfunction "PB13_43") (pintype "bidirectional"))
    )
    (net (code "167") (name "unconnected-(J1C-PB14-Pad45)") (class "Default")
      (node (ref "J1") (pin "45") (pinfunction "PB14_45") (pintype "bidirectional"))
    )
    (net (code "168") (name "unconnected-(J1C-PB15-Pad47)") (class "Default")
      (node (ref "J1") (pin "47") (pinfunction "PB15_47") (pintype "bidirectional"))
    )
    (net (code "169") (name "unconnected-(J1C-PC8-Pad69)") (class "Default")
      (node (ref "J1") (pin "69") (pinfunction "PC8_69") (pintype "bidirectional"))
    )
    (net (code "170") (name "unconnected-(J1C-PC9-Pad71)") (class "Default")
      (node (ref "J1") (pin "71") (pinfunction "PC9_71") (pintype "bidirectional"))
    )
    (net (code "171") (name "unconnected-(J1C-PD8-Pad49)") (class "Default")
      (node (ref "J1") (pin "49") (pinfunction "PD8_49") (pintype "bidirectional"))
    )
    (net (code "172") (name "unconnected-(J1C-PD9-Pad51)") (class "Default")
      (node (ref "J1") (pin "51") (pinfunction "PD9_51") (pintype "bidirectional"))
    )
    (net (code "173") (name "unconnected-(J1C-PD10-Pad53)") (class "Default")
      (node (ref "J1") (pin "53") (pinfunction "PD10_53") (pintype "bidirectional"))
    )
    (net (code "174") (name "unconnected-(J1C-PD11-Pad55)") (class "Default")
      (node (ref "J1") (pin "55") (pinfunction "PD11_55") (pintype "bidirectional"))
    )
    (net (code "175") (name "unconnected-(J1C-PD12-Pad57)") (class "Default")
      (node (ref "J1") (pin "57") (pinfunction "PD12_57") (pintype "bidirectional"))
    )
    (net (code "176") (name "unconnected-(J1C-PD13-Pad59)") (class "Default")
      (node (ref "J1") (pin "59") (pinfunction "PD13_59") (pintype "bidirectional"))
    )
    (net (code "177") (name "unconnected-(J1D-PB4-Pad109)") (class "Default")
      (node (ref "J1") (pin "109") (pinfunction "PB4_109") (pintype "bidirectional"))
    )
    (net (code "178") (name "unconnected-(J1D-PB5-Pad111)") (class "Default")
      (node (ref "J1") (pin "111") (pinfunction "PB5_111") (pintype "bidirectional"))
    )
    (net (code "179") (name "unconnected-(J1D-PB6-Pad113)") (class "Default")
      (node (ref "J1") (pin "113") (pinfunction "PB6_113") (pintype "bidirectional"))
    )
    (net (code "180") (name "unconnected-(J1D-PB7-Pad115)") (class "Default")
      (node (ref "J1") (pin "115") (pinfunction "PB7_115") (pintype "bidirectional"))
    )
    (net (code "181") (name "unconnected-(J1D-PB8-Pad117)") (class "Default")
      (node (ref "J1") (pin "117") (pinfunction "PB8_117") (pintype "bidirectional"))
    )
    (net (code "182") (name "unconnected-(J1D-PB9-Pad119)") (class "Default")
      (node (ref "J1") (pin "119") (pinfunction "PB9_119") (pintype "bidirectional"))
    )
    (net (code "183") (name "unconnected-(J1D-PC10-Pad87)") (class "Default")
      (node (ref "J1") (pin "87") (pinfunction "PC10_87") (pintype "bidirectional"))
    )
    (net (code "184") (name "unconnected-(J1D-PC11-Pad89)") (class "Default")
      (node (ref "J1") (pin "89") (pinfunction "PC11_89") (pintype "bidirectional"))
    )
    (net (code "185") (name "unconnected-(J1D-PC12-Pad91)") (class "Default")
      (node (ref "J1") (pin "91") (pinfunction "PC12_91") (pintype "bidirectional"))
    )
    (net (code "186") (name "unconnected-(J1D-PD7-Pad107)") (class "Default")
      (node (ref "J1") (pin "107") (pinfunction "PD7_107") (pintype "bidirectional"))
    )
    (net (code "187") (name "unconnected-(J1D-PE1-Pad123)") (class "Default")
      (node (ref "J1") (pin "123") (pinfunction "PE1_123") (pintype "bidirectional"))
    )
    (net (code "188") (name "unconnected-(J1E-PA0{slash}AN0-Pad153)") (class "Default")
      (node (ref "J1") (pin "153") (pinfunction "PA0/AN0_153") (pintype "bidirectional"))
    )
    (net (code "189") (name "unconnected-(J1E-PA1{slash}AN1-Pad155)") (class "Default")
      (node (ref "J1") (pin "155") (pinfunction "PA1/AN1_155") (pintype "bidirectional"))
    )
    (net (code "190") (name "unconnected-(J1E-PA2{slash}AN2-Pad157)") (class "Default")
      (node (ref "J1") (pin "157") (pinfunction "PA2/AN2_157") (pintype "bidirectional"))
    )
    (net (code "191") (name "unconnected-(J1E-PC0{slash}AN10-Pad145)") (class "Default")
      (node (ref "J1") (pin "145") (pinfunction "PC0/AN10_145") (pintype "bidirectional"))
    )
    (net (code "192") (name "unconnected-(J1E-PC1{slash}AN11-Pad147)") (class "Default")
      (node (ref "J1") (pin "147") (pinfunction "PC1/AN11_147") (pintype "bidirectional"))
    )
    (net (code "193") (name "unconnected-(J1E-PC2{slash}AN12-Pad149)") (class "Default")
      (node (ref "J1") (pin "149") (pinfunction "PC2/AN12_149") (pintype "bidirectional"))
    )
    (net (code "194") (name "unconnected-(J1E-PC3{slash}AN13-Pad151)") (class "Default")
      (node (ref "J1") (pin "151") (pinfunction "PC3/AN13_151") (pintype "bidirectional"))
    )
    (net (code "195") (name "unconnected-(J1E-PC13-Pad143)") (class "Default")
      (node (ref "J1") (pin "143") (pinfunction "PC13_143") (pintype "bidirectional"))
    )
    (net (code "196") (name "unconnected-(J1E-PE2-Pad133)") (class "Default")
      (node (ref "J1") (pin "133") (pinfunction "PE2_133") (pintype "bidirectional"))
    )
    (net (code "197") (name "unconnected-(J1E-PE3-Pad135)") (class "Default")
      (node (ref "J1") (pin "135") (pinfunction "PE3_135") (pintype "bidirectional"))
    )
    (net (code "198") (name "unconnected-(J1E-PE4-Pad137)") (class "Default")
      (node (ref "J1") (pin "137") (pinfunction "PE4_137") (pintype "bidirectional"))
    )
    (net (code "199") (name "unconnected-(J1E-PE5-Pad139)") (class "Default")
      (node (ref "J1") (pin "139") (pinfunction "PE5_139") (pintype "bidirectional"))
    )
    (net (code "200") (name "unconnected-(J1E-PE6-Pad141)") (class "Default")
      (node (ref "J1") (pin "141") (pinfunction "PE6_141") (pintype "bidirectional"))
    )
    (net (code "201") (name "unconnected-(JTAG1-Pad11)") (class "Default")
      (node (ref "JTAG1") (pin "11") (pinfunction "11_11") (pintype "passive"))
    )
    (net (code "202") (name "unconnected-(JTAG1-Pad17)") (class "Default")
      (node (ref "JTAG1") (pin "17") (pinfunction "17_17") (pintype "passive"))
    )
    (net (code "203") (name "unconnected-(JTAG1-Pad19)") (class "Default")
      (node (ref "JTAG1") (pin "19") (pinfunction "19_19") (pintype "passive"))
    )
    (net (code "204") (name "unconnected-(SW1-O1-PadP$1)") (class "Default")
      (node (ref "SW1") (pin "P$1") (pinfunction "O1_P$1") (pintype "passive"))
    )
    (net (code "205") (name "unconnected-(SW1-O2-PadP$6)") (class "Default")
      (node (ref "SW1") (pin "P$6") (pinfunction "O2_P$6") (pintype "passive"))
    )
    (net (code "206") (name "unconnected-(U$4-CH-Pad11)") (class "Default")
      (node (ref "U$4") (pin "11") (pinfunction "CH_11") (pintype "bidirectional"))
    )
    (net (code "207") (name "unconnected-(U$4-IN6-Pad7)") (class "Default")
      (node (ref "U$4") (pin "7") (pinfunction "IN6_7") (pintype "bidirectional"))
    )
    (net (code "208") (name "unconnected-(U$4-IN7-Pad8)") (class "Default")
      (node (ref "U$4") (pin "8") (pinfunction "IN7_8") (pintype "bidirectional"))
    )
    (net (code "209") (name "unconnected-(U$4-IN8-Pad9)") (class "Default")
      (node (ref "U$4") (pin "9") (pinfunction "IN8_9") (pintype "bidirectional"))
    )
    (net (code "210") (name "unconnected-(U$4-OUT6-Pad14)") (class "Default")
      (node (ref "U$4") (pin "14") (pinfunction "OUT6_14") (pintype "bidirectional"))
    )
    (net (code "211") (name "unconnected-(U$4-OUT7-Pad13)") (class "Default")
      (node (ref "U$4") (pin "13") (pinfunction "OUT7_13") (pintype "bidirectional"))
    )
    (net (code "212") (name "unconnected-(U$4-OUT8-Pad12)") (class "Default")
      (node (ref "U$4") (pin "12") (pinfunction "OUT8_12") (pintype "bidirectional"))
    )
    (net (code "213") (name "unconnected-(U$5-CH-Pad11)") (class "Default")
      (node (ref "U$5") (pin "11") (pinfunction "CH_11") (pintype "bidirectional"))
    )
    (net (code "214") (name "unconnected-(U$5-IN1-Pad2)") (class "Default")
      (node (ref "U$5") (pin "2") (pinfunction "IN1_2") (pintype "bidirectional"))
    )
    (net (code "215") (name "unconnected-(U$5-OUT1-Pad19)") (class "Default")
      (node (ref "U$5") (pin "19") (pinfunction "OUT1_19") (pintype "bidirectional"))
    )
    (net (code "216") (name "unconnected-(U$8-{slash}OUT15-Pad23)") (class "Default")
      (node (ref "U$8") (pin "23") (pinfunction "/OUT15_23") (pintype "bidirectional"))
    )
    (net (code "217") (name "unconnected-(U$30-{slash}OUT15-Pad23)") (class "Default")
      (node (ref "U$30") (pin "23") (pinfunction "/OUT15_23") (pintype "bidirectional"))
    )
    (net (code "218") (name "unconnected-(U$33-{slash}OUT15-Pad23)") (class "Default")
      (node (ref "U$33") (pin "23") (pinfunction "/OUT15_23") (pintype "bidirectional"))
    )
    (net (code "219") (name "unconnected-(U$36-{slash}OUT15-Pad23)") (class "Default")
      (node (ref "U$36") (pin "23") (pinfunction "/OUT15_23") (pintype "bidirectional"))
    )
    (net (code "220") (name "unconnected-(U$51-{slash}OUT15-Pad23)") (class "Default")
      (node (ref "U$51") (pin "23") (pinfunction "/OUT15_23") (pintype "bidirectional"))
    )
    (net (code "221") (name "unconnected-(U10-NC-Pad8)") (class "Default")
      (node (ref "U10") (pin "8") (pinfunction "NC_8") (pintype "no_connect"))
    )
    (net (code "222") (name "unconnected-(U10-NC_2-Pad5)") (class "Default")
      (node (ref "U10") (pin "5") (pinfunction "NC_2_5") (pintype "no_connect"))
    )
    (net (code "223") (name "~{RESET}") (class "Default")
      (node (ref "J1") (pin "1") (pinfunction "PA3/AN3_1") (pintype "bidirectional"))
      (node (ref "U$30") (pin "25") (pinfunction "/RESET_25") (pintype "bidirectional"))
      (node (ref "U$33") (pin "25") (pinfunction "/RESET_25") (pintype "bidirectional"))
      (node (ref "U$36") (pin "25") (pinfunction "/RESET_25") (pintype "bidirectional"))
      (node (ref "U$51") (pin "25") (pinfunction "/RESET_25") (pintype "bidirectional"))
      (node (ref "U$8") (pin "25") (pinfunction "/RESET_25") (pintype "bidirectional"))
    )
  )
)
